# bop_pcb.net
KiCad netlist of a schematic drawn in EAGLE
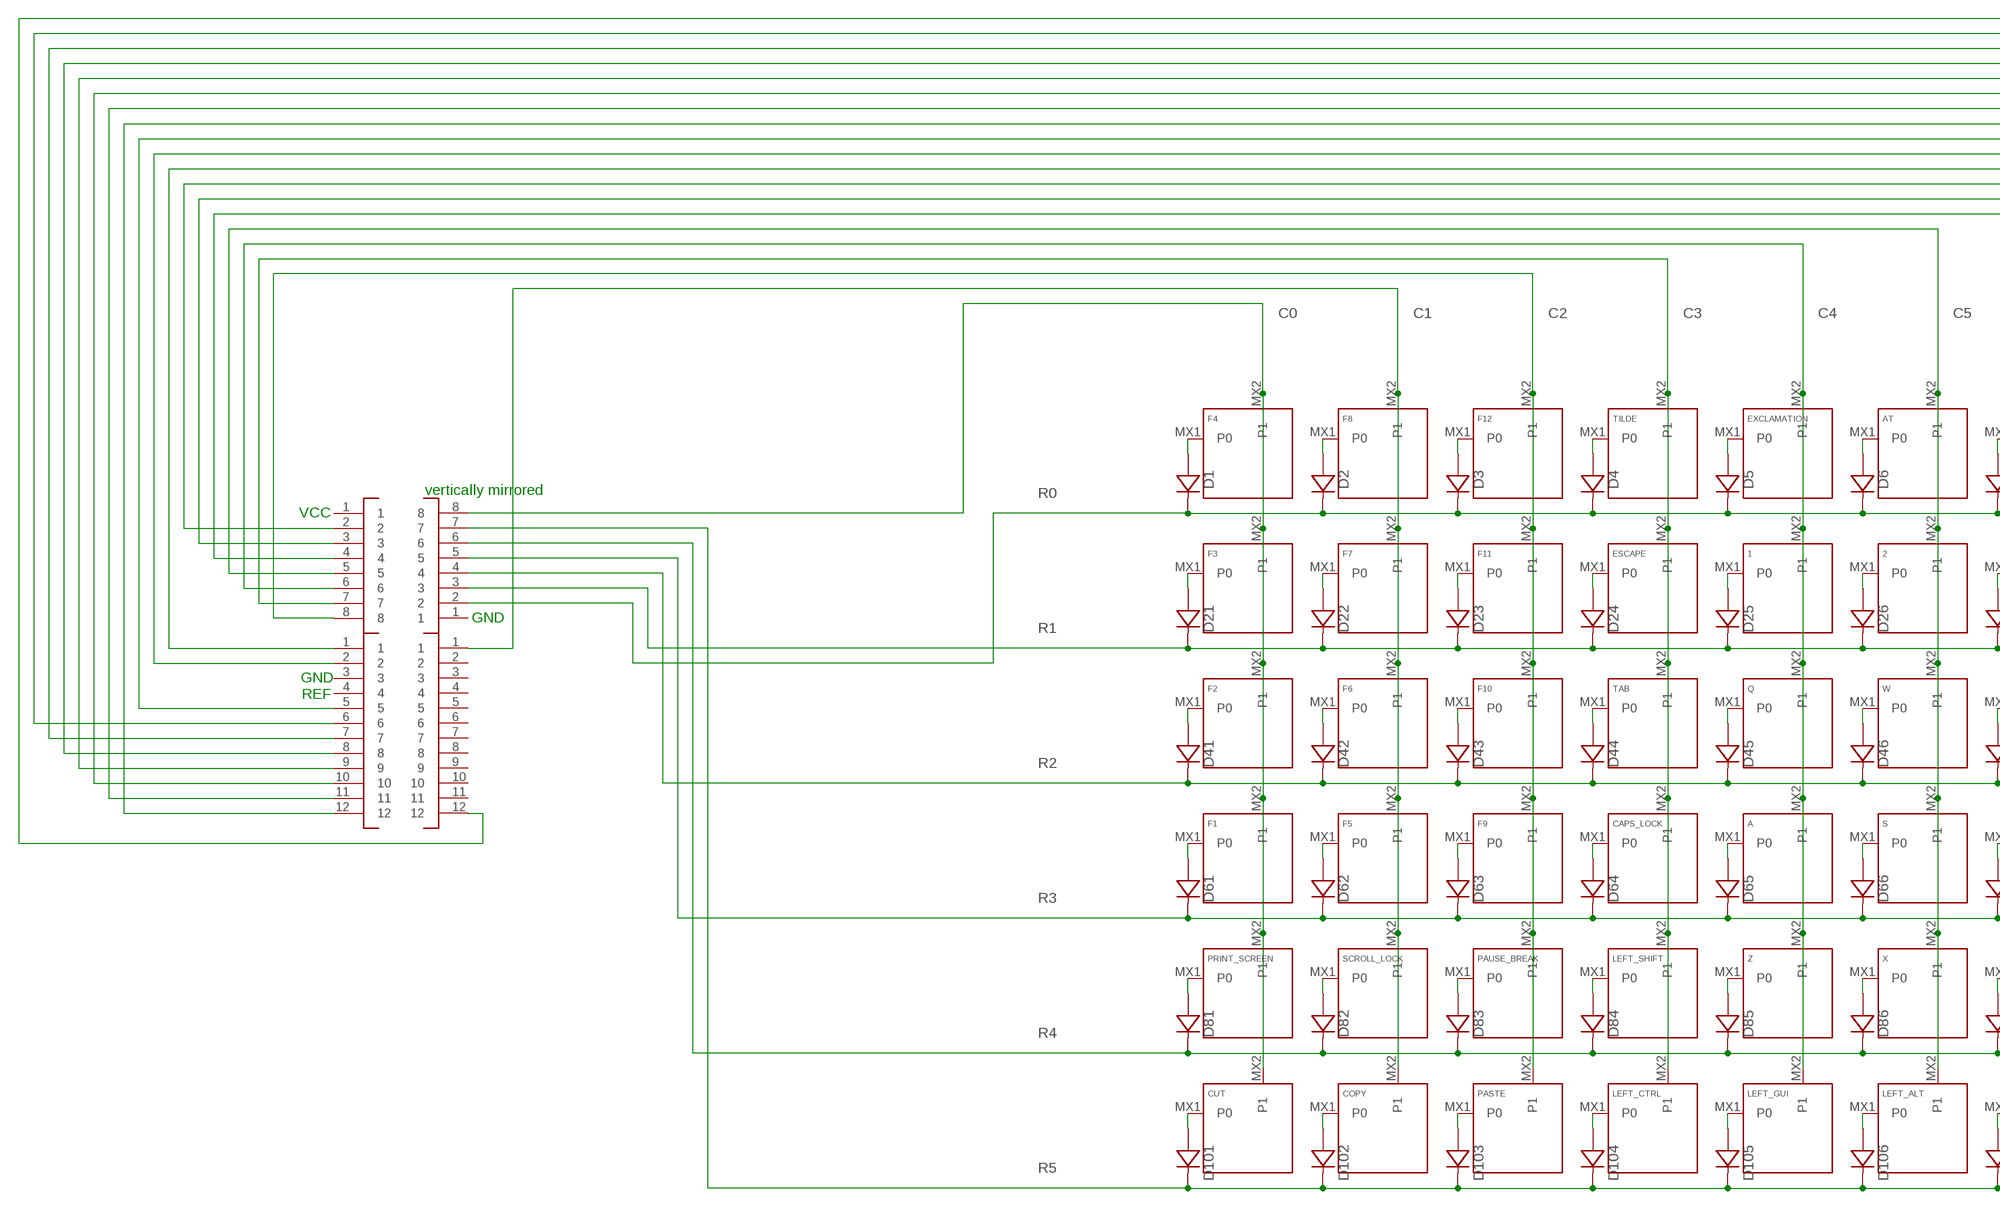
[diagram p0: schematic, sheet 1, part 1 of 2]
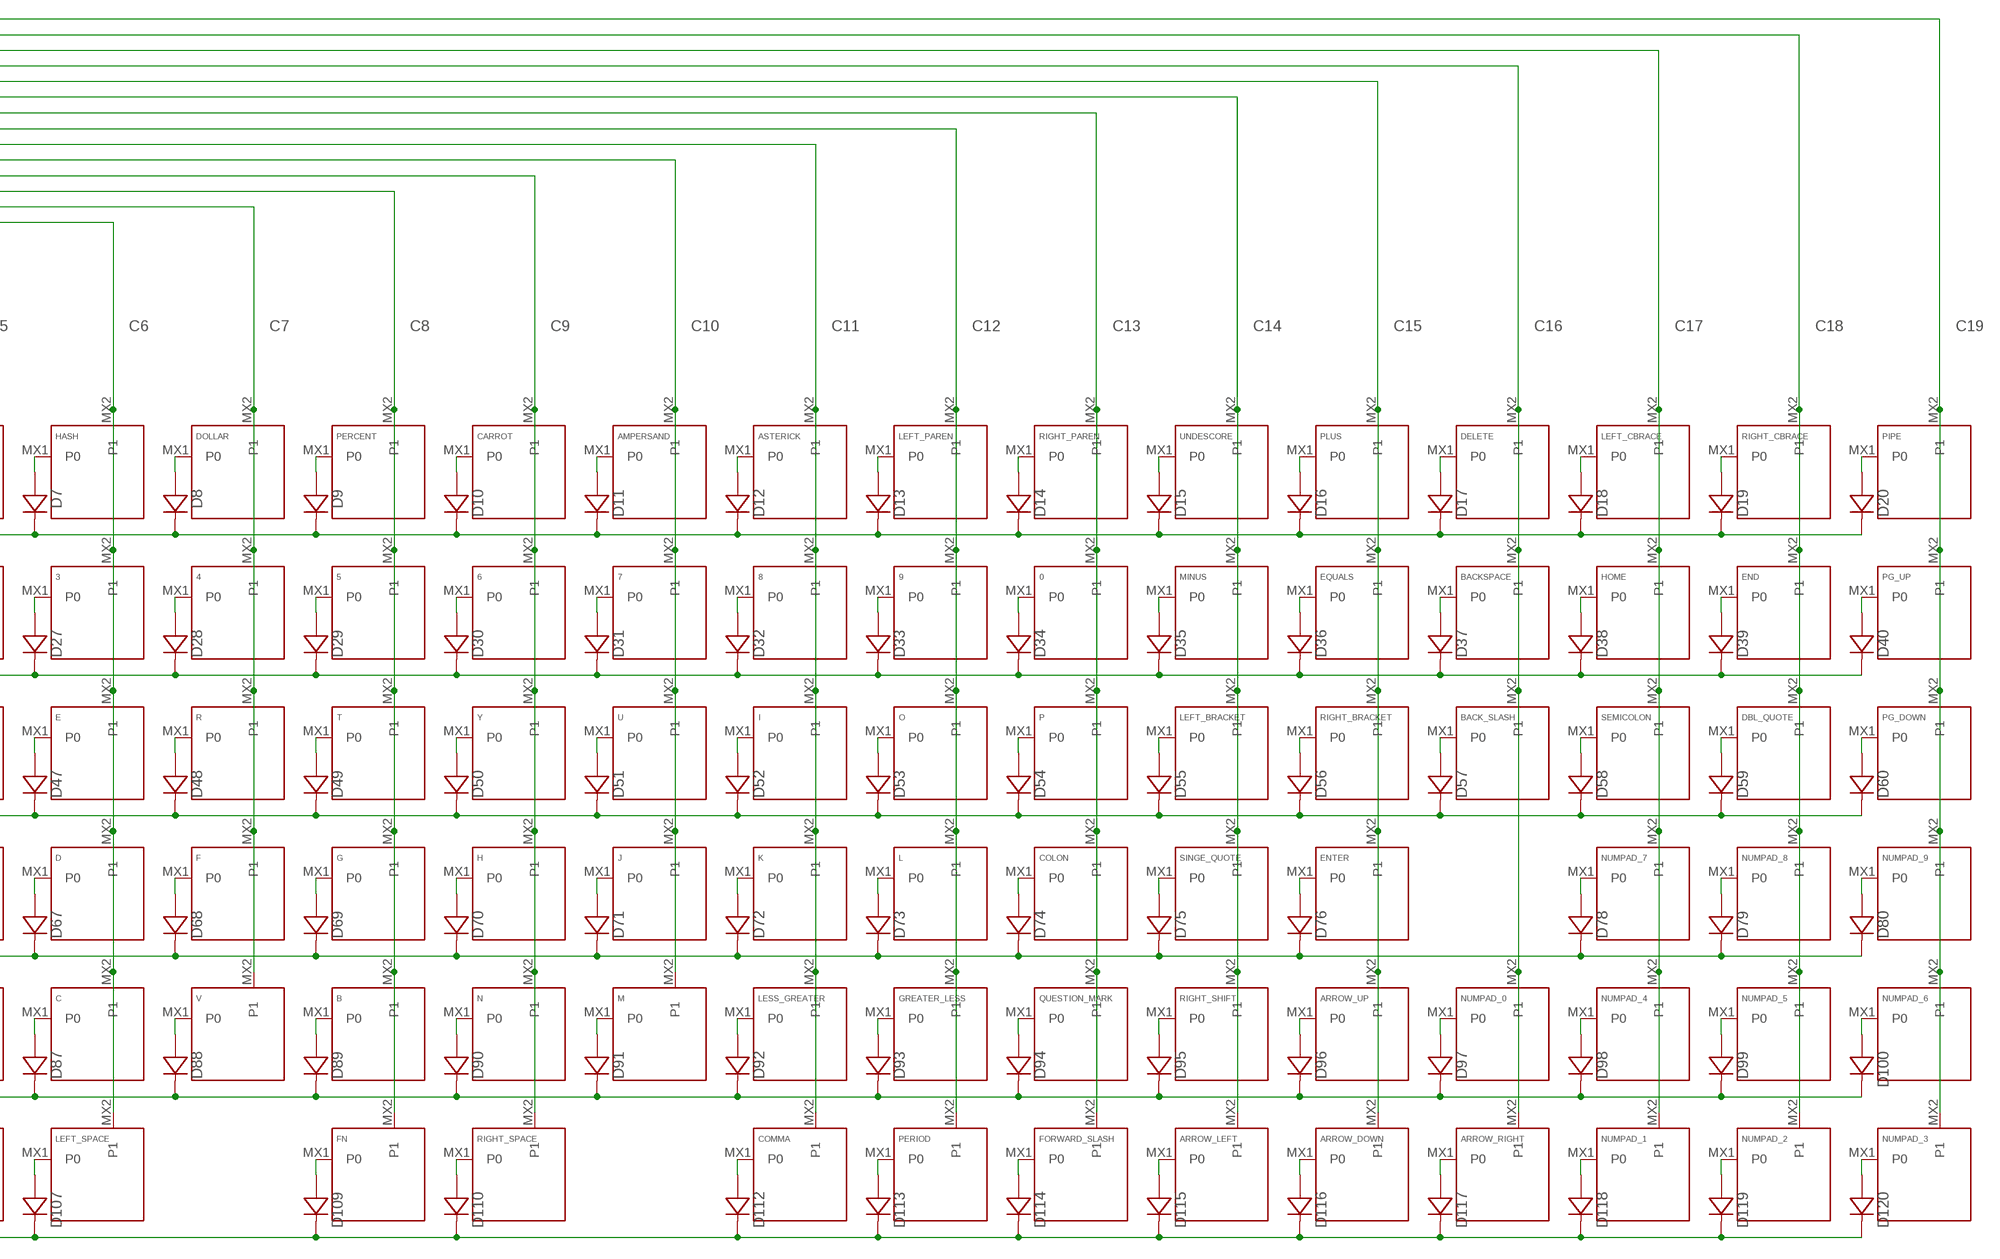
[diagram p1: schematic, sheet 1, part 2 of 2]

(export (version "E")
  (design (tool "Eeschema 10.0.6"))
  (components
    (comp (ref "0")
      (value "KEYSWITCH-PLAIN-MX-1U")
      (footprint "eagle-import:MX-1U")
      (libsource (lib "eagle-import") (part "KEYSWITCH-PLAIN-MX-1U"))
    )
    (comp (ref "1")
      (value "KEYSWITCH-PLAIN-MX-1U")
      (footprint "eagle-import:MX-1U")
      (libsource (lib "eagle-import") (part "KEYSWITCH-PLAIN-MX-1U"))
    )
    (comp (ref "2")
      (value "KEYSWITCH-PLAIN-MX-1U")
      (footprint "eagle-import:MX-1U")
      (libsource (lib "eagle-import") (part "KEYSWITCH-PLAIN-MX-1U"))
    )
    (comp (ref "3")
      (value "KEYSWITCH-PLAIN-MX-1U")
      (footprint "eagle-import:MX-1U")
      (libsource (lib "eagle-import") (part "KEYSWITCH-PLAIN-MX-1U"))
    )
    (comp (ref "4")
      (value "KEYSWITCH-PLAIN-MX-1U")
      (footprint "eagle-import:MX-1U")
      (libsource (lib "eagle-import") (part "KEYSWITCH-PLAIN-MX-1U"))
    )
    (comp (ref "5")
      (value "KEYSWITCH-PLAIN-MX-1U")
      (footprint "eagle-import:MX-1U")
      (libsource (lib "eagle-import") (part "KEYSWITCH-PLAIN-MX-1U"))
    )
    (comp (ref "6")
      (value "KEYSWITCH-PLAIN-MX-1U")
      (footprint "eagle-import:MX-1U")
      (libsource (lib "eagle-import") (part "KEYSWITCH-PLAIN-MX-1U"))
    )
    (comp (ref "7")
      (value "KEYSWITCH-PLAIN-MX-1U")
      (footprint "eagle-import:MX-1U")
      (libsource (lib "eagle-import") (part "KEYSWITCH-PLAIN-MX-1U"))
    )
    (comp (ref "8")
      (value "KEYSWITCH-PLAIN-MX-1U")
      (footprint "eagle-import:MX-1U")
      (libsource (lib "eagle-import") (part "KEYSWITCH-PLAIN-MX-1U"))
    )
    (comp (ref "9")
      (value "KEYSWITCH-PLAIN-MX-1U")
      (footprint "eagle-import:MX-1U")
      (libsource (lib "eagle-import") (part "KEYSWITCH-PLAIN-MX-1U"))
    )
    (comp (ref "A")
      (value "KEYSWITCH-PLAIN-MX-1U")
      (footprint "eagle-import:MX-1U")
      (libsource (lib "eagle-import") (part "KEYSWITCH-PLAIN-MX-1U"))
    )
    (comp (ref "AMPERSAND")
      (value "KEYSWITCH-PLAIN-MX-1U")
      (footprint "eagle-import:MX-1U")
      (libsource (lib "eagle-import") (part "KEYSWITCH-PLAIN-MX-1U"))
    )
    (comp (ref "ARROW_DOWN")
      (value "KEYSWITCH-PLAIN-MX-1U")
      (footprint "eagle-import:MX-1U")
      (libsource (lib "eagle-import") (part "KEYSWITCH-PLAIN-MX-1U"))
    )
    (comp (ref "ARROW_LEFT")
      (value "KEYSWITCH-PLAIN-MX-1U")
      (footprint "eagle-import:MX-1U")
      (libsource (lib "eagle-import") (part "KEYSWITCH-PLAIN-MX-1U"))
    )
    (comp (ref "ARROW_RIGHT")
      (value "KEYSWITCH-PLAIN-MX-1U")
      (footprint "eagle-import:MX-1U")
      (libsource (lib "eagle-import") (part "KEYSWITCH-PLAIN-MX-1U"))
    )
    (comp (ref "ARROW_UP")
      (value "KEYSWITCH-PLAIN-MX-1U")
      (footprint "eagle-import:MX-1U")
      (libsource (lib "eagle-import") (part "KEYSWITCH-PLAIN-MX-1U"))
    )
    (comp (ref "ASTERICK")
      (value "KEYSWITCH-PLAIN-MX-1U")
      (footprint "eagle-import:MX-1U")
      (libsource (lib "eagle-import") (part "KEYSWITCH-PLAIN-MX-1U"))
    )
    (comp (ref "AT")
      (value "KEYSWITCH-PLAIN-MX-1U")
      (footprint "eagle-import:MX-1U")
      (libsource (lib "eagle-import") (part "KEYSWITCH-PLAIN-MX-1U"))
    )
    (comp (ref "B")
      (value "KEYSWITCH-PLAIN-MX-1U")
      (footprint "eagle-import:MX-1U")
      (libsource (lib "eagle-import") (part "KEYSWITCH-PLAIN-MX-1U"))
    )
    (comp (ref "BACKSPACE")
      (value "KEYSWITCH-PLAIN-MX-1U")
      (footprint "eagle-import:MX-1U")
      (libsource (lib "eagle-import") (part "KEYSWITCH-PLAIN-MX-1U"))
    )
    (comp (ref "BACK_SLASH")
      (value "KEYSWITCH-PLAIN-MX-1U")
      (footprint "eagle-import:MX-1U")
      (libsource (lib "eagle-import") (part "KEYSWITCH-PLAIN-MX-1U"))
    )
    (comp (ref "C")
      (value "KEYSWITCH-PLAIN-MX-1U")
      (footprint "eagle-import:MX-1U")
      (libsource (lib "eagle-import") (part "KEYSWITCH-PLAIN-MX-1U"))
    )
    (comp (ref "CAPS_LOCK")
      (value "KEYSWITCH-PLAIN-MX-1U")
      (footprint "eagle-import:MX-1U")
      (libsource (lib "eagle-import") (part "KEYSWITCH-PLAIN-MX-1U"))
    )
    (comp (ref "CARROT")
      (value "KEYSWITCH-PLAIN-MX-1U")
      (footprint "eagle-import:MX-1U")
      (libsource (lib "eagle-import") (part "KEYSWITCH-PLAIN-MX-1U"))
    )
    (comp (ref "COLON")
      (value "KEYSWITCH-PLAIN-MX-1U")
      (footprint "eagle-import:MX-1U")
      (libsource (lib "eagle-import") (part "KEYSWITCH-PLAIN-MX-1U"))
    )
    (comp (ref "COMMA")
      (value "KEYSWITCH-PLAIN-MX-1U")
      (footprint "eagle-import:MX-1U")
      (libsource (lib "eagle-import") (part "KEYSWITCH-PLAIN-MX-1U"))
    )
    (comp (ref "COPY")
      (value "KEYSWITCH-PLAIN-MX-1U")
      (footprint "eagle-import:MX-1U")
      (libsource (lib "eagle-import") (part "KEYSWITCH-PLAIN-MX-1U"))
    )
    (comp (ref "CUT")
      (value "KEYSWITCH-PLAIN-MX-1U")
      (footprint "eagle-import:MX-1U")
      (libsource (lib "eagle-import") (part "KEYSWITCH-PLAIN-MX-1U"))
    )
    (comp (ref "D")
      (value "KEYSWITCH-PLAIN-MX-1U")
      (footprint "eagle-import:MX-1U")
      (libsource (lib "eagle-import") (part "KEYSWITCH-PLAIN-MX-1U"))
    )
    (comp (ref "D1")
      (value "DIODE-SOD-123")
      (footprint "eagle-import:SOD-123")
      (libsource (lib "eagle-import") (part "DIODE-SOD-123"))
    )
    (comp (ref "D2")
      (value "DIODE-SOD-123")
      (footprint "eagle-import:SOD-123")
      (libsource (lib "eagle-import") (part "DIODE-SOD-123"))
    )
    (comp (ref "D3")
      (value "DIODE-SOD-123")
      (footprint "eagle-import:SOD-123")
      (libsource (lib "eagle-import") (part "DIODE-SOD-123"))
    )
    (comp (ref "D4")
      (value "DIODE-SOD-123")
      (footprint "eagle-import:SOD-123")
      (libsource (lib "eagle-import") (part "DIODE-SOD-123"))
    )
    (comp (ref "D5")
      (value "DIODE-SOD-123")
      (footprint "eagle-import:SOD-123")
      (libsource (lib "eagle-import") (part "DIODE-SOD-123"))
    )
    (comp (ref "D6")
      (value "DIODE-SOD-123")
      (footprint "eagle-import:SOD-123")
      (libsource (lib "eagle-import") (part "DIODE-SOD-123"))
    )
    (comp (ref "D7")
      (value "DIODE-SOD-123")
      (footprint "eagle-import:SOD-123")
      (libsource (lib "eagle-import") (part "DIODE-SOD-123"))
    )
    (comp (ref "D8")
      (value "DIODE-SOD-123")
      (footprint "eagle-import:SOD-123")
      (libsource (lib "eagle-import") (part "DIODE-SOD-123"))
    )
    (comp (ref "D9")
      (value "DIODE-SOD-123")
      (footprint "eagle-import:SOD-123")
      (libsource (lib "eagle-import") (part "DIODE-SOD-123"))
    )
    (comp (ref "D10")
      (value "DIODE-SOD-123")
      (footprint "eagle-import:SOD-123")
      (libsource (lib "eagle-import") (part "DIODE-SOD-123"))
    )
    (comp (ref "D11")
      (value "DIODE-SOD-123")
      (footprint "eagle-import:SOD-123")
      (libsource (lib "eagle-import") (part "DIODE-SOD-123"))
    )
    (comp (ref "D12")
      (value "DIODE-SOD-123")
      (footprint "eagle-import:SOD-123")
      (libsource (lib "eagle-import") (part "DIODE-SOD-123"))
    )
    (comp (ref "D13")
      (value "DIODE-SOD-123")
      (footprint "eagle-import:SOD-123")
      (libsource (lib "eagle-import") (part "DIODE-SOD-123"))
    )
    (comp (ref "D14")
      (value "DIODE-SOD-123")
      (footprint "eagle-import:SOD-123")
      (libsource (lib "eagle-import") (part "DIODE-SOD-123"))
    )
    (comp (ref "D15")
      (value "DIODE-SOD-123")
      (footprint "eagle-import:SOD-123")
      (libsource (lib "eagle-import") (part "DIODE-SOD-123"))
    )
    (comp (ref "D16")
      (value "DIODE-SOD-123")
      (footprint "eagle-import:SOD-123")
      (libsource (lib "eagle-import") (part "DIODE-SOD-123"))
    )
    (comp (ref "D17")
      (value "DIODE-SOD-123")
      (footprint "eagle-import:SOD-123")
      (libsource (lib "eagle-import") (part "DIODE-SOD-123"))
    )
    (comp (ref "D18")
      (value "DIODE-SOD-123")
      (footprint "eagle-import:SOD-123")
      (libsource (lib "eagle-import") (part "DIODE-SOD-123"))
    )
    (comp (ref "D19")
      (value "DIODE-SOD-123")
      (footprint "eagle-import:SOD-123")
      (libsource (lib "eagle-import") (part "DIODE-SOD-123"))
    )
    (comp (ref "D20")
      (value "DIODE-SOD-123")
      (footprint "eagle-import:SOD-123")
      (libsource (lib "eagle-import") (part "DIODE-SOD-123"))
    )
    (comp (ref "D21")
      (value "DIODE-SOD-123")
      (footprint "eagle-import:SOD-123")
      (libsource (lib "eagle-import") (part "DIODE-SOD-123"))
    )
    (comp (ref "D22")
      (value "DIODE-SOD-123")
      (footprint "eagle-import:SOD-123")
      (libsource (lib "eagle-import") (part "DIODE-SOD-123"))
    )
    (comp (ref "D23")
      (value "DIODE-SOD-123")
      (footprint "eagle-import:SOD-123")
      (libsource (lib "eagle-import") (part "DIODE-SOD-123"))
    )
    (comp (ref "D24")
      (value "DIODE-SOD-123")
      (footprint "eagle-import:SOD-123")
      (libsource (lib "eagle-import") (part "DIODE-SOD-123"))
    )
    (comp (ref "D25")
      (value "DIODE-SOD-123")
      (footprint "eagle-import:SOD-123")
      (libsource (lib "eagle-import") (part "DIODE-SOD-123"))
    )
    (comp (ref "D26")
      (value "DIODE-SOD-123")
      (footprint "eagle-import:SOD-123")
      (libsource (lib "eagle-import") (part "DIODE-SOD-123"))
    )
    (comp (ref "D27")
      (value "DIODE-SOD-123")
      (footprint "eagle-import:SOD-123")
      (libsource (lib "eagle-import") (part "DIODE-SOD-123"))
    )
    (comp (ref "D28")
      (value "DIODE-SOD-123")
      (footprint "eagle-import:SOD-123")
      (libsource (lib "eagle-import") (part "DIODE-SOD-123"))
    )
    (comp (ref "D29")
      (value "DIODE-SOD-123")
      (footprint "eagle-import:SOD-123")
      (libsource (lib "eagle-import") (part "DIODE-SOD-123"))
    )
    (comp (ref "D30")
      (value "DIODE-SOD-123")
      (footprint "eagle-import:SOD-123")
      (libsource (lib "eagle-import") (part "DIODE-SOD-123"))
    )
    (comp (ref "D31")
      (value "DIODE-SOD-123")
      (footprint "eagle-import:SOD-123")
      (libsource (lib "eagle-import") (part "DIODE-SOD-123"))
    )
    (comp (ref "D32")
      (value "DIODE-SOD-123")
      (footprint "eagle-import:SOD-123")
      (libsource (lib "eagle-import") (part "DIODE-SOD-123"))
    )
    (comp (ref "D33")
      (value "DIODE-SOD-123")
      (footprint "eagle-import:SOD-123")
      (libsource (lib "eagle-import") (part "DIODE-SOD-123"))
    )
    (comp (ref "D34")
      (value "DIODE-SOD-123")
      (footprint "eagle-import:SOD-123")
      (libsource (lib "eagle-import") (part "DIODE-SOD-123"))
    )
    (comp (ref "D35")
      (value "DIODE-SOD-123")
      (footprint "eagle-import:SOD-123")
      (libsource (lib "eagle-import") (part "DIODE-SOD-123"))
    )
    (comp (ref "D36")
      (value "DIODE-SOD-123")
      (footprint "eagle-import:SOD-123")
      (libsource (lib "eagle-import") (part "DIODE-SOD-123"))
    )
    (comp (ref "D37")
      (value "DIODE-SOD-123")
      (footprint "eagle-import:SOD-123")
      (libsource (lib "eagle-import") (part "DIODE-SOD-123"))
    )
    (comp (ref "D38")
      (value "DIODE-SOD-123")
      (footprint "eagle-import:SOD-123")
      (libsource (lib "eagle-import") (part "DIODE-SOD-123"))
    )
    (comp (ref "D39")
      (value "DIODE-SOD-123")
      (footprint "eagle-import:SOD-123")
      (libsource (lib "eagle-import") (part "DIODE-SOD-123"))
    )
    (comp (ref "D40")
      (value "DIODE-SOD-123")
      (footprint "eagle-import:SOD-123")
      (libsource (lib "eagle-import") (part "DIODE-SOD-123"))
    )
    (comp (ref "D41")
      (value "DIODE-SOD-123")
      (footprint "eagle-import:SOD-123")
      (libsource (lib "eagle-import") (part "DIODE-SOD-123"))
    )
    (comp (ref "D42")
      (value "DIODE-SOD-123")
      (footprint "eagle-import:SOD-123")
      (libsource (lib "eagle-import") (part "DIODE-SOD-123"))
    )
    (comp (ref "D43")
      (value "DIODE-SOD-123")
      (footprint "eagle-import:SOD-123")
      (libsource (lib "eagle-import") (part "DIODE-SOD-123"))
    )
    (comp (ref "D44")
      (value "DIODE-SOD-123")
      (footprint "eagle-import:SOD-123")
      (libsource (lib "eagle-import") (part "DIODE-SOD-123"))
    )
    (comp (ref "D45")
      (value "DIODE-SOD-123")
      (footprint "eagle-import:SOD-123")
      (libsource (lib "eagle-import") (part "DIODE-SOD-123"))
    )
    (comp (ref "D46")
      (value "DIODE-SOD-123")
      (footprint "eagle-import:SOD-123")
      (libsource (lib "eagle-import") (part "DIODE-SOD-123"))
    )
    (comp (ref "D47")
      (value "DIODE-SOD-123")
      (footprint "eagle-import:SOD-123")
      (libsource (lib "eagle-import") (part "DIODE-SOD-123"))
    )
    (comp (ref "D48")
      (value "DIODE-SOD-123")
      (footprint "eagle-import:SOD-123")
      (libsource (lib "eagle-import") (part "DIODE-SOD-123"))
    )
    (comp (ref "D49")
      (value "DIODE-SOD-123")
      (footprint "eagle-import:SOD-123")
      (libsource (lib "eagle-import") (part "DIODE-SOD-123"))
    )
    (comp (ref "D50")
      (value "DIODE-SOD-123")
      (footprint "eagle-import:SOD-123")
      (libsource (lib "eagle-import") (part "DIODE-SOD-123"))
    )
    (comp (ref "D51")
      (value "DIODE-SOD-123")
      (footprint "eagle-import:SOD-123")
      (libsource (lib "eagle-import") (part "DIODE-SOD-123"))
    )
    (comp (ref "D52")
      (value "DIODE-SOD-123")
      (footprint "eagle-import:SOD-123")
      (libsource (lib "eagle-import") (part "DIODE-SOD-123"))
    )
    (comp (ref "D53")
      (value "DIODE-SOD-123")
      (footprint "eagle-import:SOD-123")
      (libsource (lib "eagle-import") (part "DIODE-SOD-123"))
    )
    (comp (ref "D54")
      (value "DIODE-SOD-123")
      (footprint "eagle-import:SOD-123")
      (libsource (lib "eagle-import") (part "DIODE-SOD-123"))
    )
    (comp (ref "D55")
      (value "DIODE-SOD-123")
      (footprint "eagle-import:SOD-123")
      (libsource (lib "eagle-import") (part "DIODE-SOD-123"))
    )
    (comp (ref "D56")
      (value "DIODE-SOD-123")
      (footprint "eagle-import:SOD-123")
      (libsource (lib "eagle-import") (part "DIODE-SOD-123"))
    )
    (comp (ref "D57")
      (value "DIODE-SOD-123")
      (footprint "eagle-import:SOD-123")
      (libsource (lib "eagle-import") (part "DIODE-SOD-123"))
    )
    (comp (ref "D58")
      (value "DIODE-SOD-123")
      (footprint "eagle-import:SOD-123")
      (libsource (lib "eagle-import") (part "DIODE-SOD-123"))
    )
    (comp (ref "D59")
      (value "DIODE-SOD-123")
      (footprint "eagle-import:SOD-123")
      (libsource (lib "eagle-import") (part "DIODE-SOD-123"))
    )
    (comp (ref "D60")
      (value "DIODE-SOD-123")
      (footprint "eagle-import:SOD-123")
      (libsource (lib "eagle-import") (part "DIODE-SOD-123"))
    )
    (comp (ref "D61")
      (value "DIODE-SOD-123")
      (footprint "eagle-import:SOD-123")
      (libsource (lib "eagle-import") (part "DIODE-SOD-123"))
    )
    (comp (ref "D62")
      (value "DIODE-SOD-123")
      (footprint "eagle-import:SOD-123")
      (libsource (lib "eagle-import") (part "DIODE-SOD-123"))
    )
    (comp (ref "D63")
      (value "DIODE-SOD-123")
      (footprint "eagle-import:SOD-123")
      (libsource (lib "eagle-import") (part "DIODE-SOD-123"))
    )
    (comp (ref "D64")
      (value "DIODE-SOD-123")
      (footprint "eagle-import:SOD-123")
      (libsource (lib "eagle-import") (part "DIODE-SOD-123"))
    )
    (comp (ref "D65")
      (value "DIODE-SOD-123")
      (footprint "eagle-import:SOD-123")
      (libsource (lib "eagle-import") (part "DIODE-SOD-123"))
    )
    (comp (ref "D66")
      (value "DIODE-SOD-123")
      (footprint "eagle-import:SOD-123")
      (libsource (lib "eagle-import") (part "DIODE-SOD-123"))
    )
    (comp (ref "D67")
      (value "DIODE-SOD-123")
      (footprint "eagle-import:SOD-123")
      (libsource (lib "eagle-import") (part "DIODE-SOD-123"))
    )
    (comp (ref "D68")
      (value "DIODE-SOD-123")
      (footprint "eagle-import:SOD-123")
      (libsource (lib "eagle-import") (part "DIODE-SOD-123"))
    )
    (comp (ref "D69")
      (value "DIODE-SOD-123")
      (footprint "eagle-import:SOD-123")
      (libsource (lib "eagle-import") (part "DIODE-SOD-123"))
    )
    (comp (ref "D70")
      (value "DIODE-SOD-123")
      (footprint "eagle-import:SOD-123")
      (libsource (lib "eagle-import") (part "DIODE-SOD-123"))
    )
    (comp (ref "D71")
      (value "DIODE-SOD-123")
      (footprint "eagle-import:SOD-123")
      (libsource (lib "eagle-import") (part "DIODE-SOD-123"))
    )
    (comp (ref "D72")
      (value "DIODE-SOD-123")
      (footprint "eagle-import:SOD-123")
      (libsource (lib "eagle-import") (part "DIODE-SOD-123"))
    )
    (comp (ref "D73")
      (value "DIODE-SOD-123")
      (footprint "eagle-import:SOD-123")
      (libsource (lib "eagle-import") (part "DIODE-SOD-123"))
    )
    (comp (ref "D74")
      (value "DIODE-SOD-123")
      (footprint "eagle-import:SOD-123")
      (libsource (lib "eagle-import") (part "DIODE-SOD-123"))
    )
    (comp (ref "D75")
      (value "DIODE-SOD-123")
      (footprint "eagle-import:SOD-123")
      (libsource (lib "eagle-import") (part "DIODE-SOD-123"))
    )
    (comp (ref "D76")
      (value "DIODE-SOD-123")
      (footprint "eagle-import:SOD-123")
      (libsource (lib "eagle-import") (part "DIODE-SOD-123"))
    )
    (comp (ref "D78")
      (value "DIODE-SOD-123")
      (footprint "eagle-import:SOD-123")
      (libsource (lib "eagle-import") (part "DIODE-SOD-123"))
    )
    (comp (ref "D79")
      (value "DIODE-SOD-123")
      (footprint "eagle-import:SOD-123")
      (libsource (lib "eagle-import") (part "DIODE-SOD-123"))
    )
    (comp (ref "D80")
      (value "DIODE-SOD-123")
      (footprint "eagle-import:SOD-123")
      (libsource (lib "eagle-import") (part "DIODE-SOD-123"))
    )
    (comp (ref "D81")
      (value "DIODE-SOD-123")
      (footprint "eagle-import:SOD-123")
      (libsource (lib "eagle-import") (part "DIODE-SOD-123"))
    )
    (comp (ref "D82")
      (value "DIODE-SOD-123")
      (footprint "eagle-import:SOD-123")
      (libsource (lib "eagle-import") (part "DIODE-SOD-123"))
    )
    (comp (ref "D83")
      (value "DIODE-SOD-123")
      (footprint "eagle-import:SOD-123")
      (libsource (lib "eagle-import") (part "DIODE-SOD-123"))
    )
    (comp (ref "D84")
      (value "DIODE-SOD-123")
      (footprint "eagle-import:SOD-123")
      (libsource (lib "eagle-import") (part "DIODE-SOD-123"))
    )
    (comp (ref "D85")
      (value "DIODE-SOD-123")
      (footprint "eagle-import:SOD-123")
      (libsource (lib "eagle-import") (part "DIODE-SOD-123"))
    )
    (comp (ref "D86")
      (value "DIODE-SOD-123")
      (footprint "eagle-import:SOD-123")
      (libsource (lib "eagle-import") (part "DIODE-SOD-123"))
    )
    (comp (ref "D87")
      (value "DIODE-SOD-123")
      (footprint "eagle-import:SOD-123")
      (libsource (lib "eagle-import") (part "DIODE-SOD-123"))
    )
    (comp (ref "D88")
      (value "DIODE-SOD-123")
      (footprint "eagle-import:SOD-123")
      (libsource (lib "eagle-import") (part "DIODE-SOD-123"))
    )
    (comp (ref "D89")
      (value "DIODE-SOD-123")
      (footprint "eagle-import:SOD-123")
      (libsource (lib "eagle-import") (part "DIODE-SOD-123"))
    )
    (comp (ref "D90")
      (value "DIODE-SOD-123")
      (footprint "eagle-import:SOD-123")
      (libsource (lib "eagle-import") (part "DIODE-SOD-123"))
    )
    (comp (ref "D91")
      (value "DIODE-SOD-123")
      (footprint "eagle-import:SOD-123")
      (libsource (lib "eagle-import") (part "DIODE-SOD-123"))
    )
    (comp (ref "D92")
      (value "DIODE-SOD-123")
      (footprint "eagle-import:SOD-123")
      (libsource (lib "eagle-import") (part "DIODE-SOD-123"))
    )
    (comp (ref "D93")
      (value "DIODE-SOD-123")
      (footprint "eagle-import:SOD-123")
      (libsource (lib "eagle-import") (part "DIODE-SOD-123"))
    )
    (comp (ref "D94")
      (value "DIODE-SOD-123")
      (footprint "eagle-import:SOD-123")
      (libsource (lib "eagle-import") (part "DIODE-SOD-123"))
    )
    (comp (ref "D95")
      (value "DIODE-SOD-123")
      (footprint "eagle-import:SOD-123")
      (libsource (lib "eagle-import") (part "DIODE-SOD-123"))
    )
    (comp (ref "D96")
      (value "DIODE-SOD-123")
      (footprint "eagle-import:SOD-123")
      (libsource (lib "eagle-import") (part "DIODE-SOD-123"))
    )
    (comp (ref "D97")
      (value "DIODE-SOD-123")
      (footprint "eagle-import:SOD-123")
      (libsource (lib "eagle-import") (part "DIODE-SOD-123"))
    )
    (comp (ref "D98")
      (value "DIODE-SOD-123")
      (footprint "eagle-import:SOD-123")
      (libsource (lib "eagle-import") (part "DIODE-SOD-123"))
    )
    (comp (ref "D99")
      (value "DIODE-SOD-123")
      (footprint "eagle-import:SOD-123")
      (libsource (lib "eagle-import") (part "DIODE-SOD-123"))
    )
    (comp (ref "D100")
      (value "DIODE-SOD-123")
      (footprint "eagle-import:SOD-123")
      (libsource (lib "eagle-import") (part "DIODE-SOD-123"))
    )
    (comp (ref "D101")
      (value "DIODE-SOD-123")
      (footprint "eagle-import:SOD-123")
      (libsource (lib "eagle-import") (part "DIODE-SOD-123"))
    )
    (comp (ref "D102")
      (value "DIODE-SOD-123")
      (footprint "eagle-import:SOD-123")
      (libsource (lib "eagle-import") (part "DIODE-SOD-123"))
    )
    (comp (ref "D103")
      (value "DIODE-SOD-123")
      (footprint "eagle-import:SOD-123")
      (libsource (lib "eagle-import") (part "DIODE-SOD-123"))
    )
    (comp (ref "D104")
      (value "DIODE-SOD-123")
      (footprint "eagle-import:SOD-123")
      (libsource (lib "eagle-import") (part "DIODE-SOD-123"))
    )
    (comp (ref "D105")
      (value "DIODE-SOD-123")
      (footprint "eagle-import:SOD-123")
      (libsource (lib "eagle-import") (part "DIODE-SOD-123"))
    )
    (comp (ref "D106")
      (value "DIODE-SOD-123")
      (footprint "eagle-import:SOD-123")
      (libsource (lib "eagle-import") (part "DIODE-SOD-123"))
    )
    (comp (ref "D107")
      (value "DIODE-SOD-123")
      (footprint "eagle-import:SOD-123")
      (libsource (lib "eagle-import") (part "DIODE-SOD-123"))
    )
    (comp (ref "D109")
      (value "DIODE-SOD-123")
      (footprint "eagle-import:SOD-123")
      (libsource (lib "eagle-import") (part "DIODE-SOD-123"))
    )
    (comp (ref "D110")
      (value "DIODE-SOD-123")
      (footprint "eagle-import:SOD-123")
      (libsource (lib "eagle-import") (part "DIODE-SOD-123"))
    )
    (comp (ref "D112")
      (value "DIODE-SOD-123")
      (footprint "eagle-import:SOD-123")
      (libsource (lib "eagle-import") (part "DIODE-SOD-123"))
    )
    (comp (ref "D113")
      (value "DIODE-SOD-123")
      (footprint "eagle-import:SOD-123")
      (libsource (lib "eagle-import") (part "DIODE-SOD-123"))
    )
    (comp (ref "D114")
      (value "DIODE-SOD-123")
      (footprint "eagle-import:SOD-123")
      (libsource (lib "eagle-import") (part "DIODE-SOD-123"))
    )
    (comp (ref "D115")
      (value "DIODE-SOD-123")
      (footprint "eagle-import:SOD-123")
      (libsource (lib "eagle-import") (part "DIODE-SOD-123"))
    )
    (comp (ref "D116")
      (value "DIODE-SOD-123")
      (footprint "eagle-import:SOD-123")
      (libsource (lib "eagle-import") (part "DIODE-SOD-123"))
    )
    (comp (ref "D117")
      (value "DIODE-SOD-123")
      (footprint "eagle-import:SOD-123")
      (libsource (lib "eagle-import") (part "DIODE-SOD-123"))
    )
    (comp (ref "D118")
      (value "DIODE-SOD-123")
      (footprint "eagle-import:SOD-123")
      (libsource (lib "eagle-import") (part "DIODE-SOD-123"))
    )
    (comp (ref "D119")
      (value "DIODE-SOD-123")
      (footprint "eagle-import:SOD-123")
      (libsource (lib "eagle-import") (part "DIODE-SOD-123"))
    )
    (comp (ref "D120")
      (value "DIODE-SOD-123")
      (footprint "eagle-import:SOD-123")
      (libsource (lib "eagle-import") (part "DIODE-SOD-123"))
    )
    (comp (ref "DBL_QUOTE")
      (value "KEYSWITCH-PLAIN-MX-1U")
      (footprint "eagle-import:MX-1U")
      (libsource (lib "eagle-import") (part "KEYSWITCH-PLAIN-MX-1U"))
    )
    (comp (ref "DELETE")
      (value "KEYSWITCH-PLAIN-MX-1U")
      (footprint "eagle-import:MX-1U")
      (libsource (lib "eagle-import") (part "KEYSWITCH-PLAIN-MX-1U"))
    )
    (comp (ref "DOLLAR")
      (value "KEYSWITCH-PLAIN-MX-1U")
      (footprint "eagle-import:MX-1U")
      (libsource (lib "eagle-import") (part "KEYSWITCH-PLAIN-MX-1U"))
    )
    (comp (ref "E")
      (value "KEYSWITCH-PLAIN-MX-1U")
      (footprint "eagle-import:MX-1U")
      (libsource (lib "eagle-import") (part "KEYSWITCH-PLAIN-MX-1U"))
    )
    (comp (ref "END")
      (value "KEYSWITCH-PLAIN-MX-1U")
      (footprint "eagle-import:MX-1U")
      (libsource (lib "eagle-import") (part "KEYSWITCH-PLAIN-MX-1U"))
    )
    (comp (ref "ENTER")
      (value "KEYSWITCH-PLAIN-MX-1U")
      (footprint "eagle-import:MX-1U")
      (libsource (lib "eagle-import") (part "KEYSWITCH-PLAIN-MX-1U"))
    )
    (comp (ref "EQUALS")
      (value "KEYSWITCH-PLAIN-MX-1U")
      (footprint "eagle-import:MX-1U")
      (libsource (lib "eagle-import") (part "KEYSWITCH-PLAIN-MX-1U"))
    )
    (comp (ref "ESCAPE")
      (value "KEYSWITCH-PLAIN-MX-1U")
      (footprint "eagle-import:MX-1U")
      (libsource (lib "eagle-import") (part "KEYSWITCH-PLAIN-MX-1U"))
    )
    (comp (ref "EXCLAMATION")
      (value "KEYSWITCH-PLAIN-MX-1U")
      (footprint "eagle-import:MX-1U")
      (libsource (lib "eagle-import") (part "KEYSWITCH-PLAIN-MX-1U"))
    )
    (comp (ref "F")
      (value "KEYSWITCH-PLAIN-MX-1U")
      (footprint "eagle-import:MX-1U")
      (libsource (lib "eagle-import") (part "KEYSWITCH-PLAIN-MX-1U"))
    )
    (comp (ref "F1")
      (value "KEYSWITCH-PLAIN-MX-1U")
      (footprint "eagle-import:MX-1U")
      (libsource (lib "eagle-import") (part "KEYSWITCH-PLAIN-MX-1U"))
    )
    (comp (ref "F2")
      (value "KEYSWITCH-PLAIN-MX-1U")
      (footprint "eagle-import:MX-1U")
      (libsource (lib "eagle-import") (part "KEYSWITCH-PLAIN-MX-1U"))
    )
    (comp (ref "F3")
      (value "KEYSWITCH-PLAIN-MX-1U")
      (footprint "eagle-import:MX-1U")
      (libsource (lib "eagle-import") (part "KEYSWITCH-PLAIN-MX-1U"))
    )
    (comp (ref "F4")
      (value "KEYSWITCH-PLAIN-MX-1U")
      (footprint "eagle-import:MX-1U")
      (libsource (lib "eagle-import") (part "KEYSWITCH-PLAIN-MX-1U"))
    )
    (comp (ref "F5")
      (value "KEYSWITCH-PLAIN-MX-1U")
      (footprint "eagle-import:MX-1U")
      (libsource (lib "eagle-import") (part "KEYSWITCH-PLAIN-MX-1U"))
    )
    (comp (ref "F6")
      (value "KEYSWITCH-PLAIN-MX-1U")
      (footprint "eagle-import:MX-1U")
      (libsource (lib "eagle-import") (part "KEYSWITCH-PLAIN-MX-1U"))
    )
    (comp (ref "F7")
      (value "KEYSWITCH-PLAIN-MX-1U")
      (footprint "eagle-import:MX-1U")
      (libsource (lib "eagle-import") (part "KEYSWITCH-PLAIN-MX-1U"))
    )
    (comp (ref "F8")
      (value "KEYSWITCH-PLAIN-MX-1U")
      (footprint "eagle-import:MX-1U")
      (libsource (lib "eagle-import") (part "KEYSWITCH-PLAIN-MX-1U"))
    )
    (comp (ref "F9")
      (value "KEYSWITCH-PLAIN-MX-1U")
      (footprint "eagle-import:MX-1U")
      (libsource (lib "eagle-import") (part "KEYSWITCH-PLAIN-MX-1U"))
    )
    (comp (ref "F10")
      (value "KEYSWITCH-PLAIN-MX-1U")
      (footprint "eagle-import:MX-1U")
      (libsource (lib "eagle-import") (part "KEYSWITCH-PLAIN-MX-1U"))
    )
    (comp (ref "F11")
      (value "KEYSWITCH-PLAIN-MX-1U")
      (footprint "eagle-import:MX-1U")
      (libsource (lib "eagle-import") (part "KEYSWITCH-PLAIN-MX-1U"))
    )
    (comp (ref "F12")
      (value "KEYSWITCH-PLAIN-MX-1U")
      (footprint "eagle-import:MX-1U")
      (libsource (lib "eagle-import") (part "KEYSWITCH-PLAIN-MX-1U"))
    )
    (comp (ref "FN")
      (value "KEYSWITCH-PLAIN-MX-1U")
      (footprint "eagle-import:MX-1U")
      (libsource (lib "eagle-import") (part "KEYSWITCH-PLAIN-MX-1U"))
    )
    (comp (ref "FORWARD_SLASH")
      (value "KEYSWITCH-PLAIN-MX-1U")
      (footprint "eagle-import:MX-1U")
      (libsource (lib "eagle-import") (part "KEYSWITCH-PLAIN-MX-1U"))
    )
    (comp (ref "G")
      (value "KEYSWITCH-PLAIN-MX-1U")
      (footprint "eagle-import:MX-1U")
      (libsource (lib "eagle-import") (part "KEYSWITCH-PLAIN-MX-1U"))
    )
    (comp (ref "GREATER_LESS")
      (value "KEYSWITCH-PLAIN-MX-1U")
      (footprint "eagle-import:MX-1U")
      (libsource (lib "eagle-import") (part "KEYSWITCH-PLAIN-MX-1U"))
    )
    (comp (ref "H")
      (value "KEYSWITCH-PLAIN-MX-1U")
      (footprint "eagle-import:MX-1U")
      (libsource (lib "eagle-import") (part "KEYSWITCH-PLAIN-MX-1U"))
    )
    (comp (ref "HASH")
      (value "KEYSWITCH-PLAIN-MX-1U")
      (footprint "eagle-import:MX-1U")
      (libsource (lib "eagle-import") (part "KEYSWITCH-PLAIN-MX-1U"))
    )
    (comp (ref "HOME")
      (value "KEYSWITCH-PLAIN-MX-1U")
      (footprint "eagle-import:MX-1U")
      (libsource (lib "eagle-import") (part "KEYSWITCH-PLAIN-MX-1U"))
    )
    (comp (ref "I")
      (value "KEYSWITCH-PLAIN-MX-1U")
      (footprint "eagle-import:MX-1U")
      (libsource (lib "eagle-import") (part "KEYSWITCH-PLAIN-MX-1U"))
    )
    (comp (ref "J")
      (value "KEYSWITCH-PLAIN-MX-1U")
      (footprint "eagle-import:MX-1U")
      (libsource (lib "eagle-import") (part "KEYSWITCH-PLAIN-MX-1U"))
    )
    (comp (ref "J1")
      (value "HEADER-12X1-2.54-ROUND")
      (footprint "eagle-import:HEADER-12X1-2.54-ROUND")
      (libsource (lib "eagle-import") (part "HEADER-12X1-2.54-ROUND"))
    )
    (comp (ref "J2")
      (value "HEADER-12X1-2.54-ROUND")
      (footprint "eagle-import:HEADER-12X1-2.54-ROUND")
      (libsource (lib "eagle-import") (part "HEADER-12X1-2.54-ROUND"))
    )
    (comp (ref "K")
      (value "KEYSWITCH-PLAIN-MX-1U")
      (footprint "eagle-import:MX-1U")
      (libsource (lib "eagle-import") (part "KEYSWITCH-PLAIN-MX-1U"))
    )
    (comp (ref "L")
      (value "KEYSWITCH-PLAIN-MX-1U")
      (footprint "eagle-import:MX-1U")
      (libsource (lib "eagle-import") (part "KEYSWITCH-PLAIN-MX-1U"))
    )
    (comp (ref "LEFT_ALT")
      (value "KEYSWITCH-PLAIN-MX-1U")
      (footprint "eagle-import:MX-1U")
      (libsource (lib "eagle-import") (part "KEYSWITCH-PLAIN-MX-1U"))
    )
    (comp (ref "LEFT_BRACKET")
      (value "KEYSWITCH-PLAIN-MX-1U")
      (footprint "eagle-import:MX-1U")
      (libsource (lib "eagle-import") (part "KEYSWITCH-PLAIN-MX-1U"))
    )
    (comp (ref "LEFT_CBRACE")
      (value "KEYSWITCH-PLAIN-MX-1U")
      (footprint "eagle-import:MX-1U")
      (libsource (lib "eagle-import") (part "KEYSWITCH-PLAIN-MX-1U"))
    )
    (comp (ref "LEFT_CTRL")
      (value "KEYSWITCH-PLAIN-MX-1U")
      (footprint "eagle-import:MX-1U")
      (libsource (lib "eagle-import") (part "KEYSWITCH-PLAIN-MX-1U"))
    )
    (comp (ref "LEFT_GUI")
      (value "KEYSWITCH-PLAIN-MX-1U")
      (footprint "eagle-import:MX-1U")
      (libsource (lib "eagle-import") (part "KEYSWITCH-PLAIN-MX-1U"))
    )
    (comp (ref "LEFT_PAREN")
      (value "KEYSWITCH-PLAIN-MX-1U")
      (footprint "eagle-import:MX-1U")
      (libsource (lib "eagle-import") (part "KEYSWITCH-PLAIN-MX-1U"))
    )
    (comp (ref "LEFT_SHIFT")
      (value "KEYSWITCH-PLAIN-MX-1U")
      (footprint "eagle-import:MX-1U")
      (libsource (lib "eagle-import") (part "KEYSWITCH-PLAIN-MX-1U"))
    )
    (comp (ref "LEFT_SPACE")
      (value "KEYSWITCH-PLAIN-MX-2U-FLIPPED")
      (footprint "eagle-import:MX-2U-FLIPPED")
      (libsource (lib "eagle-import") (part "KEYSWITCH-PLAIN-MX-2U-FLIPPED"))
    )
    (comp (ref "LESS_GREATER")
      (value "KEYSWITCH-PLAIN-MX-1U")
      (footprint "eagle-import:MX-1U")
      (libsource (lib "eagle-import") (part "KEYSWITCH-PLAIN-MX-1U"))
    )
    (comp (ref "M")
      (value "KEYSWITCH-PLAIN-MX-1U")
      (footprint "eagle-import:MX-1U")
      (libsource (lib "eagle-import") (part "KEYSWITCH-PLAIN-MX-1U"))
    )
    (comp (ref "MINUS")
      (value "KEYSWITCH-PLAIN-MX-1U")
      (footprint "eagle-import:MX-1U")
      (libsource (lib "eagle-import") (part "KEYSWITCH-PLAIN-MX-1U"))
    )
    (comp (ref "N")
      (value "KEYSWITCH-PLAIN-MX-1U")
      (footprint "eagle-import:MX-1U")
      (libsource (lib "eagle-import") (part "KEYSWITCH-PLAIN-MX-1U"))
    )
    (comp (ref "NUMPAD_0")
      (value "KEYSWITCH-PLAIN-MX-2U-ROTATED")
      (footprint "eagle-import:MX-2U-ROTATED")
      (libsource (lib "eagle-import") (part "KEYSWITCH-PLAIN-MX-2U-ROTATED"))
    )
    (comp (ref "NUMPAD_1")
      (value "KEYSWITCH-PLAIN-MX-1U")
      (footprint "eagle-import:MX-1U")
      (libsource (lib "eagle-import") (part "KEYSWITCH-PLAIN-MX-1U"))
    )
    (comp (ref "NUMPAD_2")
      (value "KEYSWITCH-PLAIN-MX-1U")
      (footprint "eagle-import:MX-1U")
      (libsource (lib "eagle-import") (part "KEYSWITCH-PLAIN-MX-1U"))
    )
    (comp (ref "NUMPAD_3")
      (value "KEYSWITCH-PLAIN-MX-1U")
      (footprint "eagle-import:MX-1U")
      (libsource (lib "eagle-import") (part "KEYSWITCH-PLAIN-MX-1U"))
    )
    (comp (ref "NUMPAD_4")
      (value "KEYSWITCH-PLAIN-MX-1U")
      (footprint "eagle-import:MX-1U")
      (libsource (lib "eagle-import") (part "KEYSWITCH-PLAIN-MX-1U"))
    )
    (comp (ref "NUMPAD_5")
      (value "KEYSWITCH-PLAIN-MX-1U")
      (footprint "eagle-import:MX-1U")
      (libsource (lib "eagle-import") (part "KEYSWITCH-PLAIN-MX-1U"))
    )
    (comp (ref "NUMPAD_6")
      (value "KEYSWITCH-PLAIN-MX-1U")
      (footprint "eagle-import:MX-1U")
      (libsource (lib "eagle-import") (part "KEYSWITCH-PLAIN-MX-1U"))
    )
    (comp (ref "NUMPAD_7")
      (value "KEYSWITCH-PLAIN-MX-1U")
      (footprint "eagle-import:MX-1U")
      (libsource (lib "eagle-import") (part "KEYSWITCH-PLAIN-MX-1U"))
    )
    (comp (ref "NUMPAD_8")
      (value "KEYSWITCH-PLAIN-MX-1U")
      (footprint "eagle-import:MX-1U")
      (libsource (lib "eagle-import") (part "KEYSWITCH-PLAIN-MX-1U"))
    )
    (comp (ref "NUMPAD_9")
      (value "KEYSWITCH-PLAIN-MX-1U")
      (footprint "eagle-import:MX-1U")
      (libsource (lib "eagle-import") (part "KEYSWITCH-PLAIN-MX-1U"))
    )
    (comp (ref "O")
      (value "KEYSWITCH-PLAIN-MX-1U")
      (footprint "eagle-import:MX-1U")
      (libsource (lib "eagle-import") (part "KEYSWITCH-PLAIN-MX-1U"))
    )
    (comp (ref "P")
      (value "KEYSWITCH-PLAIN-MX-1U")
      (footprint "eagle-import:MX-1U")
      (libsource (lib "eagle-import") (part "KEYSWITCH-PLAIN-MX-1U"))
    )
    (comp (ref "PASTE")
      (value "KEYSWITCH-PLAIN-MX-1U")
      (footprint "eagle-import:MX-1U")
      (libsource (lib "eagle-import") (part "KEYSWITCH-PLAIN-MX-1U"))
    )
    (comp (ref "PAUSE_BREAK")
      (value "KEYSWITCH-PLAIN-MX-1U")
      (footprint "eagle-import:MX-1U")
      (libsource (lib "eagle-import") (part "KEYSWITCH-PLAIN-MX-1U"))
    )
    (comp (ref "PERCENT")
      (value "KEYSWITCH-PLAIN-MX-1U")
      (footprint "eagle-import:MX-1U")
      (libsource (lib "eagle-import") (part "KEYSWITCH-PLAIN-MX-1U"))
    )
    (comp (ref "PERIOD")
      (value "KEYSWITCH-PLAIN-MX-1U")
      (footprint "eagle-import:MX-1U")
      (libsource (lib "eagle-import") (part "KEYSWITCH-PLAIN-MX-1U"))
    )
    (comp (ref "PG_DOWN")
      (value "KEYSWITCH-PLAIN-MX-1U")
      (footprint "eagle-import:MX-1U")
      (libsource (lib "eagle-import") (part "KEYSWITCH-PLAIN-MX-1U"))
    )
    (comp (ref "PG_UP")
      (value "KEYSWITCH-PLAIN-MX-1U")
      (footprint "eagle-import:MX-1U")
      (libsource (lib "eagle-import") (part "KEYSWITCH-PLAIN-MX-1U"))
    )
    (comp (ref "PIPE")
      (value "KEYSWITCH-PLAIN-MX-1U")
      (footprint "eagle-import:MX-1U")
      (libsource (lib "eagle-import") (part "KEYSWITCH-PLAIN-MX-1U"))
    )
    (comp (ref "PLUS")
      (value "KEYSWITCH-PLAIN-MX-1U")
      (footprint "eagle-import:MX-1U")
      (libsource (lib "eagle-import") (part "KEYSWITCH-PLAIN-MX-1U"))
    )
    (comp (ref "PRINT_SCREEN")
      (value "KEYSWITCH-PLAIN-MX-1U")
      (footprint "eagle-import:MX-1U")
      (libsource (lib "eagle-import") (part "KEYSWITCH-PLAIN-MX-1U"))
    )
    (comp (ref "Q")
      (value "KEYSWITCH-PLAIN-MX-1U")
      (footprint "eagle-import:MX-1U")
      (libsource (lib "eagle-import") (part "KEYSWITCH-PLAIN-MX-1U"))
    )
    (comp (ref "QUESTION_MARK")
      (value "KEYSWITCH-PLAIN-MX-1U")
      (footprint "eagle-import:MX-1U")
      (libsource (lib "eagle-import") (part "KEYSWITCH-PLAIN-MX-1U"))
    )
    (comp (ref "R")
      (value "KEYSWITCH-PLAIN-MX-1U")
      (footprint "eagle-import:MX-1U")
      (libsource (lib "eagle-import") (part "KEYSWITCH-PLAIN-MX-1U"))
    )
    (comp (ref "RIGHT_BRACKET")
      (value "KEYSWITCH-PLAIN-MX-1U")
      (footprint "eagle-import:MX-1U")
      (libsource (lib "eagle-import") (part "KEYSWITCH-PLAIN-MX-1U"))
    )
    (comp (ref "RIGHT_CBRACE")
      (value "KEYSWITCH-PLAIN-MX-1U")
      (footprint "eagle-import:MX-1U")
      (libsource (lib "eagle-import") (part "KEYSWITCH-PLAIN-MX-1U"))
    )
    (comp (ref "RIGHT_PAREN")
      (value "KEYSWITCH-PLAIN-MX-1U")
      (footprint "eagle-import:MX-1U")
      (libsource (lib "eagle-import") (part "KEYSWITCH-PLAIN-MX-1U"))
    )
    (comp (ref "RIGHT_SHIFT")
      (value "KEYSWITCH-PLAIN-MX-1U")
      (footprint "eagle-import:MX-1U")
      (libsource (lib "eagle-import") (part "KEYSWITCH-PLAIN-MX-1U"))
    )
    (comp (ref "RIGHT_SPACE")
      (value "KEYSWITCH-PLAIN-MX-2U-FLIPPED")
      (footprint "eagle-import:MX-2U-FLIPPED")
      (libsource (lib "eagle-import") (part "KEYSWITCH-PLAIN-MX-2U-FLIPPED"))
    )
    (comp (ref "S")
      (value "KEYSWITCH-PLAIN-MX-1U")
      (footprint "eagle-import:MX-1U")
      (libsource (lib "eagle-import") (part "KEYSWITCH-PLAIN-MX-1U"))
    )
    (comp (ref "SCROLL_LOCK")
      (value "KEYSWITCH-PLAIN-MX-1U")
      (footprint "eagle-import:MX-1U")
      (libsource (lib "eagle-import") (part "KEYSWITCH-PLAIN-MX-1U"))
    )
    (comp (ref "SEMICOLON")
      (value "KEYSWITCH-PLAIN-MX-1U")
      (footprint "eagle-import:MX-1U")
      (libsource (lib "eagle-import") (part "KEYSWITCH-PLAIN-MX-1U"))
    )
    (comp (ref "SINGE_QUOTE")
      (value "KEYSWITCH-PLAIN-MX-1U")
      (footprint "eagle-import:MX-1U")
      (libsource (lib "eagle-import") (part "KEYSWITCH-PLAIN-MX-1U"))
    )
    (comp (ref "T")
      (value "KEYSWITCH-PLAIN-MX-1U")
      (footprint "eagle-import:MX-1U")
      (libsource (lib "eagle-import") (part "KEYSWITCH-PLAIN-MX-1U"))
    )
    (comp (ref "TAB")
      (value "KEYSWITCH-PLAIN-MX-1U")
      (footprint "eagle-import:MX-1U")
      (libsource (lib "eagle-import") (part "KEYSWITCH-PLAIN-MX-1U"))
    )
    (comp (ref "TILDE")
      (value "KEYSWITCH-PLAIN-MX-1U")
      (footprint "eagle-import:MX-1U")
      (libsource (lib "eagle-import") (part "KEYSWITCH-PLAIN-MX-1U"))
    )
    (comp (ref "U")
      (value "KEYSWITCH-PLAIN-MX-1U")
      (footprint "eagle-import:MX-1U")
      (libsource (lib "eagle-import") (part "KEYSWITCH-PLAIN-MX-1U"))
    )
    (comp (ref "U$1")
      (value "HEADER-8X1-2.54")
      (footprint "eagle-import:HEADER-8X1-2.54")
      (libsource (lib "eagle-import") (part "HEADER-8X1-2.54"))
    )
    (comp (ref "U$2")
      (value "HEADER-8X1-2.54")
      (footprint "eagle-import:HEADER-8X1-2.54")
      (libsource (lib "eagle-import") (part "HEADER-8X1-2.54"))
    )
    (comp (ref "UNDESCORE")
      (value "KEYSWITCH-PLAIN-MX-1U")
      (footprint "eagle-import:MX-1U")
      (libsource (lib "eagle-import") (part "KEYSWITCH-PLAIN-MX-1U"))
    )
    (comp (ref "V")
      (value "KEYSWITCH-PLAIN-MX-1U")
      (footprint "eagle-import:MX-1U")
      (libsource (lib "eagle-import") (part "KEYSWITCH-PLAIN-MX-1U"))
    )
    (comp (ref "W")
      (value "KEYSWITCH-PLAIN-MX-1U")
      (footprint "eagle-import:MX-1U")
      (libsource (lib "eagle-import") (part "KEYSWITCH-PLAIN-MX-1U"))
    )
    (comp (ref "X")
      (value "KEYSWITCH-PLAIN-MX-1U")
      (footprint "eagle-import:MX-1U")
      (libsource (lib "eagle-import") (part "KEYSWITCH-PLAIN-MX-1U"))
    )
    (comp (ref "Y")
      (value "KEYSWITCH-PLAIN-MX-1U")
      (footprint "eagle-import:MX-1U")
      (libsource (lib "eagle-import") (part "KEYSWITCH-PLAIN-MX-1U"))
    )
    (comp (ref "Z")
      (value "KEYSWITCH-PLAIN-MX-1U")
      (footprint "eagle-import:MX-1U")
      (libsource (lib "eagle-import") (part "KEYSWITCH-PLAIN-MX-1U"))
    )
  )
  (nets
    (net (code "1") (name "/C0") (class "Default")
      (node (ref "CUT") (pin "MX2") (pinfunction "P1_MX2") (pintype "bidirectional"))
      (node (ref "F1") (pin "MX2") (pinfunction "P1_MX2") (pintype "bidirectional"))
      (node (ref "F2") (pin "MX2") (pinfunction "P1_MX2") (pintype "bidirectional"))
      (node (ref "F3") (pin "MX2") (pinfunction "P1_MX2") (pintype "bidirectional"))
      (node (ref "F4") (pin "MX2") (pinfunction "P1_MX2") (pintype "bidirectional"))
      (node (ref "PRINT_SCREEN") (pin "MX2") (pinfunction "P1_MX2") (pintype "bidirectional"))
      (node (ref "U$2") (pin "8") (pinfunction "8_8") (pintype "bidirectional"))
    )
    (net (code "2") (name "/C1") (class "Default")
      (node (ref "COPY") (pin "MX2") (pinfunction "P1_MX2") (pintype "bidirectional"))
      (node (ref "F5") (pin "MX2") (pinfunction "P1_MX2") (pintype "bidirectional"))
      (node (ref "F6") (pin "MX2") (pinfunction "P1_MX2") (pintype "bidirectional"))
      (node (ref "F7") (pin "MX2") (pinfunction "P1_MX2") (pintype "bidirectional"))
      (node (ref "F8") (pin "MX2") (pinfunction "P1_MX2") (pintype "bidirectional"))
      (node (ref "J1") (pin "1") (pinfunction "1_1") (pintype "bidirectional"))
      (node (ref "SCROLL_LOCK") (pin "MX2") (pinfunction "P1_MX2") (pintype "bidirectional"))
    )
    (net (code "3") (name "/C2") (class "Default")
      (node (ref "F10") (pin "MX2") (pinfunction "P1_MX2") (pintype "bidirectional"))
      (node (ref "F11") (pin "MX2") (pinfunction "P1_MX2") (pintype "bidirectional"))
      (node (ref "F12") (pin "MX2") (pinfunction "P1_MX2") (pintype "bidirectional"))
      (node (ref "F9") (pin "MX2") (pinfunction "P1_MX2") (pintype "bidirectional"))
      (node (ref "PASTE") (pin "MX2") (pinfunction "P1_MX2") (pintype "bidirectional"))
      (node (ref "PAUSE_BREAK") (pin "MX2") (pinfunction "P1_MX2") (pintype "bidirectional"))
      (node (ref "U$1") (pin "8") (pinfunction "8_8") (pintype "bidirectional"))
    )
    (net (code "4") (name "/C3") (class "Default")
      (node (ref "CAPS_LOCK") (pin "MX2") (pinfunction "P1_MX2") (pintype "bidirectional"))
      (node (ref "ESCAPE") (pin "MX2") (pinfunction "P1_MX2") (pintype "bidirectional"))
      (node (ref "LEFT_CTRL") (pin "MX2") (pinfunction "P1_MX2") (pintype "bidirectional"))
      (node (ref "LEFT_SHIFT") (pin "MX2") (pinfunction "P1_MX2") (pintype "bidirectional"))
      (node (ref "TAB") (pin "MX2") (pinfunction "P1_MX2") (pintype "bidirectional"))
      (node (ref "TILDE") (pin "MX2") (pinfunction "P1_MX2") (pintype "bidirectional"))
      (node (ref "U$1") (pin "7") (pinfunction "7_7") (pintype "bidirectional"))
    )
    (net (code "5") (name "/C4") (class "Default")
      (node (ref "1") (pin "MX2") (pinfunction "P1_MX2") (pintype "bidirectional"))
      (node (ref "A") (pin "MX2") (pinfunction "P1_MX2") (pintype "bidirectional"))
      (node (ref "EXCLAMATION") (pin "MX2") (pinfunction "P1_MX2") (pintype "bidirectional"))
      (node (ref "LEFT_GUI") (pin "MX2") (pinfunction "P1_MX2") (pintype "bidirectional"))
      (node (ref "Q") (pin "MX2") (pinfunction "P1_MX2") (pintype "bidirectional"))
      (node (ref "U$1") (pin "6") (pinfunction "6_6") (pintype "bidirectional"))
      (node (ref "Z") (pin "MX2") (pinfunction "P1_MX2") (pintype "bidirectional"))
    )
    (net (code "6") (name "/C5") (class "Default")
      (node (ref "2") (pin "MX2") (pinfunction "P1_MX2") (pintype "bidirectional"))
      (node (ref "AT") (pin "MX2") (pinfunction "P1_MX2") (pintype "bidirectional"))
      (node (ref "LEFT_ALT") (pin "MX2") (pinfunction "P1_MX2") (pintype "bidirectional"))
      (node (ref "S") (pin "MX2") (pinfunction "P1_MX2") (pintype "bidirectional"))
      (node (ref "U$1") (pin "5") (pinfunction "5_5") (pintype "bidirectional"))
      (node (ref "W") (pin "MX2") (pinfunction "P1_MX2") (pintype "bidirectional"))
      (node (ref "X") (pin "MX2") (pinfunction "P1_MX2") (pintype "bidirectional"))
    )
    (net (code "7") (name "/C6") (class "Default")
      (node (ref "3") (pin "MX2") (pinfunction "P1_MX2") (pintype "bidirectional"))
      (node (ref "C") (pin "MX2") (pinfunction "P1_MX2") (pintype "bidirectional"))
      (node (ref "D") (pin "MX2") (pinfunction "P1_MX2") (pintype "bidirectional"))
      (node (ref "E") (pin "MX2") (pinfunction "P1_MX2") (pintype "bidirectional"))
      (node (ref "HASH") (pin "MX2") (pinfunction "P1_MX2") (pintype "bidirectional"))
      (node (ref "LEFT_SPACE") (pin "MX2") (pinfunction "P1_MX2") (pintype "bidirectional"))
      (node (ref "U$1") (pin "4") (pinfunction "4_4") (pintype "bidirectional"))
    )
    (net (code "8") (name "/C7") (class "Default")
      (node (ref "4") (pin "MX2") (pinfunction "P1_MX2") (pintype "bidirectional"))
      (node (ref "DOLLAR") (pin "MX2") (pinfunction "P1_MX2") (pintype "bidirectional"))
      (node (ref "F") (pin "MX2") (pinfunction "P1_MX2") (pintype "bidirectional"))
      (node (ref "R") (pin "MX2") (pinfunction "P1_MX2") (pintype "bidirectional"))
      (node (ref "U$1") (pin "3") (pinfunction "3_3") (pintype "bidirectional"))
      (node (ref "V") (pin "MX2") (pinfunction "P1_MX2") (pintype "bidirectional"))
    )
    (net (code "9") (name "/C8") (class "Default")
      (node (ref "5") (pin "MX2") (pinfunction "P1_MX2") (pintype "bidirectional"))
      (node (ref "B") (pin "MX2") (pinfunction "P1_MX2") (pintype "bidirectional"))
      (node (ref "FN") (pin "MX2") (pinfunction "P1_MX2") (pintype "bidirectional"))
      (node (ref "G") (pin "MX2") (pinfunction "P1_MX2") (pintype "bidirectional"))
      (node (ref "PERCENT") (pin "MX2") (pinfunction "P1_MX2") (pintype "bidirectional"))
      (node (ref "T") (pin "MX2") (pinfunction "P1_MX2") (pintype "bidirectional"))
      (node (ref "U$1") (pin "2") (pinfunction "2_2") (pintype "bidirectional"))
    )
    (net (code "10") (name "/C9") (class "Default")
      (node (ref "6") (pin "MX2") (pinfunction "P1_MX2") (pintype "bidirectional"))
      (node (ref "CARROT") (pin "MX2") (pinfunction "P1_MX2") (pintype "bidirectional"))
      (node (ref "H") (pin "MX2") (pinfunction "P1_MX2") (pintype "bidirectional"))
      (node (ref "J2") (pin "1") (pinfunction "1_1") (pintype "bidirectional"))
      (node (ref "N") (pin "MX2") (pinfunction "P1_MX2") (pintype "bidirectional"))
      (node (ref "RIGHT_SPACE") (pin "MX2") (pinfunction "P1_MX2") (pintype "bidirectional"))
      (node (ref "Y") (pin "MX2") (pinfunction "P1_MX2") (pintype "bidirectional"))
    )
    (net (code "11") (name "/C10") (class "Default")
      (node (ref "7") (pin "MX2") (pinfunction "P1_MX2") (pintype "bidirectional"))
      (node (ref "AMPERSAND") (pin "MX2") (pinfunction "P1_MX2") (pintype "bidirectional"))
      (node (ref "J") (pin "MX2") (pinfunction "P1_MX2") (pintype "bidirectional"))
      (node (ref "J2") (pin "2") (pinfunction "2_2") (pintype "bidirectional"))
      (node (ref "M") (pin "MX2") (pinfunction "P1_MX2") (pintype "bidirectional"))
      (node (ref "U") (pin "MX2") (pinfunction "P1_MX2") (pintype "bidirectional"))
    )
    (net (code "12") (name "/C11") (class "Default")
      (node (ref "8") (pin "MX2") (pinfunction "P1_MX2") (pintype "bidirectional"))
      (node (ref "ASTERICK") (pin "MX2") (pinfunction "P1_MX2") (pintype "bidirectional"))
      (node (ref "COMMA") (pin "MX2") (pinfunction "P1_MX2") (pintype "bidirectional"))
      (node (ref "I") (pin "MX2") (pinfunction "P1_MX2") (pintype "bidirectional"))
      (node (ref "J2") (pin "5") (pinfunction "5_5") (pintype "bidirectional"))
      (node (ref "K") (pin "MX2") (pinfunction "P1_MX2") (pintype "bidirectional"))
      (node (ref "LESS_GREATER") (pin "MX2") (pinfunction "P1_MX2") (pintype "bidirectional"))
    )
    (net (code "13") (name "/C12") (class "Default")
      (node (ref "9") (pin "MX2") (pinfunction "P1_MX2") (pintype "bidirectional"))
      (node (ref "GREATER_LESS") (pin "MX2") (pinfunction "P1_MX2") (pintype "bidirectional"))
      (node (ref "J2") (pin "12") (pinfunction "12_12") (pintype "bidirectional"))
      (node (ref "L") (pin "MX2") (pinfunction "P1_MX2") (pintype "bidirectional"))
      (node (ref "LEFT_PAREN") (pin "MX2") (pinfunction "P1_MX2") (pintype "bidirectional"))
      (node (ref "O") (pin "MX2") (pinfunction "P1_MX2") (pintype "bidirectional"))
      (node (ref "PERIOD") (pin "MX2") (pinfunction "P1_MX2") (pintype "bidirectional"))
    )
    (net (code "14") (name "/C13") (class "Default")
      (node (ref "0") (pin "MX2") (pinfunction "P1_MX2") (pintype "bidirectional"))
      (node (ref "COLON") (pin "MX2") (pinfunction "P1_MX2") (pintype "bidirectional"))
      (node (ref "FORWARD_SLASH") (pin "MX2") (pinfunction "P1_MX2") (pintype "bidirectional"))
      (node (ref "J2") (pin "11") (pinfunction "11_11") (pintype "bidirectional"))
      (node (ref "P") (pin "MX2") (pinfunction "P1_MX2") (pintype "bidirectional"))
      (node (ref "QUESTION_MARK") (pin "MX2") (pinfunction "P1_MX2") (pintype "bidirectional"))
      (node (ref "RIGHT_PAREN") (pin "MX2") (pinfunction "P1_MX2") (pintype "bidirectional"))
    )
    (net (code "15") (name "/C14") (class "Default")
      (node (ref "ARROW_LEFT") (pin "MX2") (pinfunction "P1_MX2") (pintype "bidirectional"))
      (node (ref "J2") (pin "10") (pinfunction "10_10") (pintype "bidirectional"))
      (node (ref "LEFT_BRACKET") (pin "MX2") (pinfunction "P1_MX2") (pintype "bidirectional"))
      (node (ref "MINUS") (pin "MX2") (pinfunction "P1_MX2") (pintype "bidirectional"))
      (node (ref "RIGHT_SHIFT") (pin "MX2") (pinfunction "P1_MX2") (pintype "bidirectional"))
      (node (ref "SINGE_QUOTE") (pin "MX2") (pinfunction "P1_MX2") (pintype "bidirectional"))
      (node (ref "UNDESCORE") (pin "MX2") (pinfunction "P1_MX2") (pintype "bidirectional"))
    )
    (net (code "16") (name "/C15") (class "Default")
      (node (ref "ARROW_DOWN") (pin "MX2") (pinfunction "P1_MX2") (pintype "bidirectional"))
      (node (ref "ARROW_UP") (pin "MX2") (pinfunction "P1_MX2") (pintype "bidirectional"))
      (node (ref "ENTER") (pin "MX2") (pinfunction "P1_MX2") (pintype "bidirectional"))
      (node (ref "EQUALS") (pin "MX2") (pinfunction "P1_MX2") (pintype "bidirectional"))
      (node (ref "J2") (pin "9") (pinfunction "9_9") (pintype "bidirectional"))
      (node (ref "PLUS") (pin "MX2") (pinfunction "P1_MX2") (pintype "bidirectional"))
      (node (ref "RIGHT_BRACKET") (pin "MX2") (pinfunction "P1_MX2") (pintype "bidirectional"))
    )
    (net (code "17") (name "/C16") (class "Default")
      (node (ref "ARROW_RIGHT") (pin "MX2") (pinfunction "P1_MX2") (pintype "bidirectional"))
      (node (ref "BACKSPACE") (pin "MX2") (pinfunction "P1_MX2") (pintype "bidirectional"))
      (node (ref "BACK_SLASH") (pin "MX2") (pinfunction "P1_MX2") (pintype "bidirectional"))
      (node (ref "DELETE") (pin "MX2") (pinfunction "P1_MX2") (pintype "bidirectional"))
      (node (ref "J2") (pin "8") (pinfunction "8_8") (pintype "bidirectional"))
      (node (ref "NUMPAD_0") (pin "MX2") (pinfunction "P1_MX2") (pintype "bidirectional"))
    )
    (net (code "18") (name "/C17") (class "Default")
      (node (ref "HOME") (pin "MX2") (pinfunction "P1_MX2") (pintype "bidirectional"))
      (node (ref "J2") (pin "7") (pinfunction "7_7") (pintype "bidirectional"))
      (node (ref "LEFT_CBRACE") (pin "MX2") (pinfunction "P1_MX2") (pintype "bidirectional"))
      (node (ref "NUMPAD_1") (pin "MX2") (pinfunction "P1_MX2") (pintype "bidirectional"))
      (node (ref "NUMPAD_4") (pin "MX2") (pinfunction "P1_MX2") (pintype "bidirectional"))
      (node (ref "NUMPAD_7") (pin "MX2") (pinfunction "P1_MX2") (pintype "bidirectional"))
      (node (ref "SEMICOLON") (pin "MX2") (pinfunction "P1_MX2") (pintype "bidirectional"))
    )
    (net (code "19") (name "/C18") (class "Default")
      (node (ref "DBL_QUOTE") (pin "MX2") (pinfunction "P1_MX2") (pintype "bidirectional"))
      (node (ref "END") (pin "MX2") (pinfunction "P1_MX2") (pintype "bidirectional"))
      (node (ref "J2") (pin "6") (pinfunction "6_6") (pintype "bidirectional"))
      (node (ref "NUMPAD_2") (pin "MX2") (pinfunction "P1_MX2") (pintype "bidirectional"))
      (node (ref "NUMPAD_5") (pin "MX2") (pinfunction "P1_MX2") (pintype "bidirectional"))
      (node (ref "NUMPAD_8") (pin "MX2") (pinfunction "P1_MX2") (pintype "bidirectional"))
      (node (ref "RIGHT_CBRACE") (pin "MX2") (pinfunction "P1_MX2") (pintype "bidirectional"))
    )
    (net (code "20") (name "/C19") (class "Default")
      (node (ref "J1") (pin "12") (pinfunction "12_12") (pintype "bidirectional"))
      (node (ref "NUMPAD_3") (pin "MX2") (pinfunction "P1_MX2") (pintype "bidirectional"))
      (node (ref "NUMPAD_6") (pin "MX2") (pinfunction "P1_MX2") (pintype "bidirectional"))
      (node (ref "NUMPAD_9") (pin "MX2") (pinfunction "P1_MX2") (pintype "bidirectional"))
      (node (ref "PG_DOWN") (pin "MX2") (pinfunction "P1_MX2") (pintype "bidirectional"))
      (node (ref "PG_UP") (pin "MX2") (pinfunction "P1_MX2") (pintype "bidirectional"))
      (node (ref "PIPE") (pin "MX2") (pinfunction "P1_MX2") (pintype "bidirectional"))
    )
    (net (code "21") (name "/R0") (class "Default")
      (node (ref "D1") (pin "C") (pinfunction "C_C") (pintype "passive"))
      (node (ref "D10") (pin "C") (pinfunction "C_C") (pintype "passive"))
      (node (ref "D11") (pin "C") (pinfunction "C_C") (pintype "passive"))
      (node (ref "D12") (pin "C") (pinfunction "C_C") (pintype "passive"))
      (node (ref "D13") (pin "C") (pinfunction "C_C") (pintype "passive"))
      (node (ref "D14") (pin "C") (pinfunction "C_C") (pintype "passive"))
      (node (ref "D15") (pin "C") (pinfunction "C_C") (pintype "passive"))
      (node (ref "D16") (pin "C") (pinfunction "C_C") (pintype "passive"))
      (node (ref "D17") (pin "C") (pinfunction "C_C") (pintype "passive"))
      (node (ref "D18") (pin "C") (pinfunction "C_C") (pintype "passive"))
      (node (ref "D19") (pin "C") (pinfunction "C_C") (pintype "passive"))
      (node (ref "D2") (pin "C") (pinfunction "C_C") (pintype "passive"))
      (node (ref "D20") (pin "C") (pinfunction "C_C") (pintype "passive"))
      (node (ref "D3") (pin "C") (pinfunction "C_C") (pintype "passive"))
      (node (ref "D4") (pin "C") (pinfunction "C_C") (pintype "passive"))
      (node (ref "D5") (pin "C") (pinfunction "C_C") (pintype "passive"))
      (node (ref "D6") (pin "C") (pinfunction "C_C") (pintype "passive"))
      (node (ref "D7") (pin "C") (pinfunction "C_C") (pintype "passive"))
      (node (ref "D8") (pin "C") (pinfunction "C_C") (pintype "passive"))
      (node (ref "D9") (pin "C") (pinfunction "C_C") (pintype "passive"))
      (node (ref "U$2") (pin "2") (pinfunction "2_2") (pintype "bidirectional"))
    )
    (net (code "22") (name "/R1") (class "Default")
      (node (ref "D21") (pin "C") (pinfunction "C_C") (pintype "passive"))
      (node (ref "D22") (pin "C") (pinfunction "C_C") (pintype "passive"))
      (node (ref "D23") (pin "C") (pinfunction "C_C") (pintype "passive"))
      (node (ref "D24") (pin "C") (pinfunction "C_C") (pintype "passive"))
      (node (ref "D25") (pin "C") (pinfunction "C_C") (pintype "passive"))
      (node (ref "D26") (pin "C") (pinfunction "C_C") (pintype "passive"))
      (node (ref "D27") (pin "C") (pinfunction "C_C") (pintype "passive"))
      (node (ref "D28") (pin "C") (pinfunction "C_C") (pintype "passive"))
      (node (ref "D29") (pin "C") (pinfunction "C_C") (pintype "passive"))
      (node (ref "D30") (pin "C") (pinfunction "C_C") (pintype "passive"))
      (node (ref "D31") (pin "C") (pinfunction "C_C") (pintype "passive"))
      (node (ref "D32") (pin "C") (pinfunction "C_C") (pintype "passive"))
      (node (ref "D33") (pin "C") (pinfunction "C_C") (pintype "passive"))
      (node (ref "D34") (pin "C") (pinfunction "C_C") (pintype "passive"))
      (node (ref "D35") (pin "C") (pinfunction "C_C") (pintype "passive"))
      (node (ref "D36") (pin "C") (pinfunction "C_C") (pintype "passive"))
      (node (ref "D37") (pin "C") (pinfunction "C_C") (pintype "passive"))
      (node (ref "D38") (pin "C") (pinfunction "C_C") (pintype "passive"))
      (node (ref "D39") (pin "C") (pinfunction "C_C") (pintype "passive"))
      (node (ref "D40") (pin "C") (pinfunction "C_C") (pintype "passive"))
      (node (ref "U$2") (pin "3") (pinfunction "3_3") (pintype "bidirectional"))
    )
    (net (code "23") (name "/R2") (class "Default")
      (node (ref "D41") (pin "C") (pinfunction "C_C") (pintype "passive"))
      (node (ref "D42") (pin "C") (pinfunction "C_C") (pintype "passive"))
      (node (ref "D43") (pin "C") (pinfunction "C_C") (pintype "passive"))
      (node (ref "D44") (pin "C") (pinfunction "C_C") (pintype "passive"))
      (node (ref "D45") (pin "C") (pinfunction "C_C") (pintype "passive"))
      (node (ref "D46") (pin "C") (pinfunction "C_C") (pintype "passive"))
      (node (ref "D47") (pin "C") (pinfunction "C_C") (pintype "passive"))
      (node (ref "D48") (pin "C") (pinfunction "C_C") (pintype "passive"))
      (node (ref "D49") (pin "C") (pinfunction "C_C") (pintype "passive"))
      (node (ref "D50") (pin "C") (pinfunction "C_C") (pintype "passive"))
      (node (ref "D51") (pin "C") (pinfunction "C_C") (pintype "passive"))
      (node (ref "D52") (pin "C") (pinfunction "C_C") (pintype "passive"))
      (node (ref "D53") (pin "C") (pinfunction "C_C") (pintype "passive"))
      (node (ref "D54") (pin "C") (pinfunction "C_C") (pintype "passive"))
      (node (ref "D55") (pin "C") (pinfunction "C_C") (pintype "passive"))
      (node (ref "D56") (pin "C") (pinfunction "C_C") (pintype "passive"))
      (node (ref "D57") (pin "C") (pinfunction "C_C") (pintype "passive"))
      (node (ref "D58") (pin "C") (pinfunction "C_C") (pintype "passive"))
      (node (ref "D59") (pin "C") (pinfunction "C_C") (pintype "passive"))
      (node (ref "D60") (pin "C") (pinfunction "C_C") (pintype "passive"))
      (node (ref "U$2") (pin "4") (pinfunction "4_4") (pintype "bidirectional"))
    )
    (net (code "24") (name "/R3") (class "Default")
      (node (ref "D61") (pin "C") (pinfunction "C_C") (pintype "passive"))
      (node (ref "D62") (pin "C") (pinfunction "C_C") (pintype "passive"))
      (node (ref "D63") (pin "C") (pinfunction "C_C") (pintype "passive"))
      (node (ref "D64") (pin "C") (pinfunction "C_C") (pintype "passive"))
      (node (ref "D65") (pin "C") (pinfunction "C_C") (pintype "passive"))
      (node (ref "D66") (pin "C") (pinfunction "C_C") (pintype "passive"))
      (node (ref "D67") (pin "C") (pinfunction "C_C") (pintype "passive"))
      (node (ref "D68") (pin "C") (pinfunction "C_C") (pintype "passive"))
      (node (ref "D69") (pin "C") (pinfunction "C_C") (pintype "passive"))
      (node (ref "D70") (pin "C") (pinfunction "C_C") (pintype "passive"))
      (node (ref "D71") (pin "C") (pinfunction "C_C") (pintype "passive"))
      (node (ref "D72") (pin "C") (pinfunction "C_C") (pintype "passive"))
      (node (ref "D73") (pin "C") (pinfunction "C_C") (pintype "passive"))
      (node (ref "D74") (pin "C") (pinfunction "C_C") (pintype "passive"))
      (node (ref "D75") (pin "C") (pinfunction "C_C") (pintype "passive"))
      (node (ref "D76") (pin "C") (pinfunction "C_C") (pintype "passive"))
      (node (ref "D78") (pin "C") (pinfunction "C_C") (pintype "passive"))
      (node (ref "D79") (pin "C") (pinfunction "C_C") (pintype "passive"))
      (node (ref "D80") (pin "C") (pinfunction "C_C") (pintype "passive"))
      (node (ref "U$2") (pin "5") (pinfunction "5_5") (pintype "bidirectional"))
    )
    (net (code "25") (name "/R4") (class "Default")
      (node (ref "D100") (pin "C") (pinfunction "C_C") (pintype "passive"))
      (node (ref "D81") (pin "C") (pinfunction "C_C") (pintype "passive"))
      (node (ref "D82") (pin "C") (pinfunction "C_C") (pintype "passive"))
      (node (ref "D83") (pin "C") (pinfunction "C_C") (pintype "passive"))
      (node (ref "D84") (pin "C") (pinfunction "C_C") (pintype "passive"))
      (node (ref "D85") (pin "C") (pinfunction "C_C") (pintype "passive"))
      (node (ref "D86") (pin "C") (pinfunction "C_C") (pintype "passive"))
      (node (ref "D87") (pin "C") (pinfunction "C_C") (pintype "passive"))
      (node (ref "D88") (pin "C") (pinfunction "C_C") (pintype "passive"))
      (node (ref "D89") (pin "C") (pinfunction "C_C") (pintype "passive"))
      (node (ref "D90") (pin "C") (pinfunction "C_C") (pintype "passive"))
      (node (ref "D91") (pin "C") (pinfunction "C_C") (pintype "passive"))
      (node (ref "D92") (pin "C") (pinfunction "C_C") (pintype "passive"))
      (node (ref "D93") (pin "C") (pinfunction "C_C") (pintype "passive"))
      (node (ref "D94") (pin "C") (pinfunction "C_C") (pintype "passive"))
      (node (ref "D95") (pin "C") (pinfunction "C_C") (pintype "passive"))
      (node (ref "D96") (pin "C") (pinfunction "C_C") (pintype "passive"))
      (node (ref "D97") (pin "C") (pinfunction "C_C") (pintype "passive"))
      (node (ref "D98") (pin "C") (pinfunction "C_C") (pintype "passive"))
      (node (ref "D99") (pin "C") (pinfunction "C_C") (pintype "passive"))
      (node (ref "U$2") (pin "6") (pinfunction "6_6") (pintype "bidirectional"))
    )
    (net (code "26") (name "/R5") (class "Default")
      (node (ref "D101") (pin "C") (pinfunction "C_C") (pintype "passive"))
      (node (ref "D102") (pin "C") (pinfunction "C_C") (pintype "passive"))
      (node (ref "D103") (pin "C") (pinfunction "C_C") (pintype "passive"))
      (node (ref "D104") (pin "C") (pinfunction "C_C") (pintype "passive"))
      (node (ref "D105") (pin "C") (pinfunction "C_C") (pintype "passive"))
      (node (ref "D106") (pin "C") (pinfunction "C_C") (pintype "passive"))
      (node (ref "D107") (pin "C") (pinfunction "C_C") (pintype "passive"))
      (node (ref "D109") (pin "C") (pinfunction "C_C") (pintype "passive"))
      (node (ref "D110") (pin "C") (pinfunction "C_C") (pintype "passive"))
      (node (ref "D112") (pin "C") (pinfunction "C_C") (pintype "passive"))
      (node (ref "D113") (pin "C") (pinfunction "C_C") (pintype "passive"))
      (node (ref "D114") (pin "C") (pinfunction "C_C") (pintype "passive"))
      (node (ref "D115") (pin "C") (pinfunction "C_C") (pintype "passive"))
      (node (ref "D116") (pin "C") (pinfunction "C_C") (pintype "passive"))
      (node (ref "D117") (pin "C") (pinfunction "C_C") (pintype "passive"))
      (node (ref "D118") (pin "C") (pinfunction "C_C") (pintype "passive"))
      (node (ref "D119") (pin "C") (pinfunction "C_C") (pintype "passive"))
      (node (ref "D120") (pin "C") (pinfunction "C_C") (pintype "passive"))
      (node (ref "U$2") (pin "7") (pinfunction "7_7") (pintype "bidirectional"))
    )
    (net (code "27") (name "Net-(0-P0)") (class "Default")
      (node (ref "0") (pin "MX1") (pinfunction "P0_MX1") (pintype "bidirectional"))
      (node (ref "D34") (pin "A") (pinfunction "A_A") (pintype "passive"))
    )
    (net (code "28") (name "Net-(1-P0)") (class "Default")
      (node (ref "1") (pin "MX1") (pinfunction "P0_MX1") (pintype "bidirectional"))
      (node (ref "D25") (pin "A") (pinfunction "A_A") (pintype "passive"))
    )
    (net (code "29") (name "Net-(2-P0)") (class "Default")
      (node (ref "2") (pin "MX1") (pinfunction "P0_MX1") (pintype "bidirectional"))
      (node (ref "D26") (pin "A") (pinfunction "A_A") (pintype "passive"))
    )
    (net (code "30") (name "Net-(3-P0)") (class "Default")
      (node (ref "3") (pin "MX1") (pinfunction "P0_MX1") (pintype "bidirectional"))
      (node (ref "D27") (pin "A") (pinfunction "A_A") (pintype "passive"))
    )
    (net (code "31") (name "Net-(4-P0)") (class "Default")
      (node (ref "4") (pin "MX1") (pinfunction "P0_MX1") (pintype "bidirectional"))
      (node (ref "D28") (pin "A") (pinfunction "A_A") (pintype "passive"))
    )
    (net (code "32") (name "Net-(5-P0)") (class "Default")
      (node (ref "5") (pin "MX1") (pinfunction "P0_MX1") (pintype "bidirectional"))
      (node (ref "D29") (pin "A") (pinfunction "A_A") (pintype "passive"))
    )
    (net (code "33") (name "Net-(6-P0)") (class "Default")
      (node (ref "6") (pin "MX1") (pinfunction "P0_MX1") (pintype "bidirectional"))
      (node (ref "D30") (pin "A") (pinfunction "A_A") (pintype "passive"))
    )
    (net (code "34") (name "Net-(7-P0)") (class "Default")
      (node (ref "7") (pin "MX1") (pinfunction "P0_MX1") (pintype "bidirectional"))
      (node (ref "D31") (pin "A") (pinfunction "A_A") (pintype "passive"))
    )
    (net (code "35") (name "Net-(8-P0)") (class "Default")
      (node (ref "8") (pin "MX1") (pinfunction "P0_MX1") (pintype "bidirectional"))
      (node (ref "D32") (pin "A") (pinfunction "A_A") (pintype "passive"))
    )
    (net (code "36") (name "Net-(9-P0)") (class "Default")
      (node (ref "9") (pin "MX1") (pinfunction "P0_MX1") (pintype "bidirectional"))
      (node (ref "D33") (pin "A") (pinfunction "A_A") (pintype "passive"))
    )
    (net (code "37") (name "Net-(A-P0)") (class "Default")
      (node (ref "A") (pin "MX1") (pinfunction "P0_MX1") (pintype "bidirectional"))
      (node (ref "D65") (pin "A") (pinfunction "A_A") (pintype "passive"))
    )
    (net (code "38") (name "Net-(AMPERSAND-P0)") (class "Default")
      (node (ref "AMPERSAND") (pin "MX1") (pinfunction "P0_MX1") (pintype "bidirectional"))
      (node (ref "D11") (pin "A") (pinfunction "A_A") (pintype "passive"))
    )
    (net (code "39") (name "Net-(ARROW_DOWN-P0)") (class "Default")
      (node (ref "ARROW_DOWN") (pin "MX1") (pinfunction "P0_MX1") (pintype "bidirectional"))
      (node (ref "D116") (pin "A") (pinfunction "A_A") (pintype "passive"))
    )
    (net (code "40") (name "Net-(ARROW_LEFT-P0)") (class "Default")
      (node (ref "ARROW_LEFT") (pin "MX1") (pinfunction "P0_MX1") (pintype "bidirectional"))
      (node (ref "D115") (pin "A") (pinfunction "A_A") (pintype "passive"))
    )
    (net (code "41") (name "Net-(ARROW_RIGHT-P0)") (class "Default")
      (node (ref "ARROW_RIGHT") (pin "MX1") (pinfunction "P0_MX1") (pintype "bidirectional"))
      (node (ref "D117") (pin "A") (pinfunction "A_A") (pintype "passive"))
    )
    (net (code "42") (name "Net-(ARROW_UP-P0)") (class "Default")
      (node (ref "ARROW_UP") (pin "MX1") (pinfunction "P0_MX1") (pintype "bidirectional"))
      (node (ref "D96") (pin "A") (pinfunction "A_A") (pintype "passive"))
    )
    (net (code "43") (name "Net-(ASTERICK-P0)") (class "Default")
      (node (ref "ASTERICK") (pin "MX1") (pinfunction "P0_MX1") (pintype "bidirectional"))
      (node (ref "D12") (pin "A") (pinfunction "A_A") (pintype "passive"))
    )
    (net (code "44") (name "Net-(AT-P0)") (class "Default")
      (node (ref "AT") (pin "MX1") (pinfunction "P0_MX1") (pintype "bidirectional"))
      (node (ref "D6") (pin "A") (pinfunction "A_A") (pintype "passive"))
    )
    (net (code "45") (name "Net-(B-P0)") (class "Default")
      (node (ref "B") (pin "MX1") (pinfunction "P0_MX1") (pintype "bidirectional"))
      (node (ref "D89") (pin "A") (pinfunction "A_A") (pintype "passive"))
    )
    (net (code "46") (name "Net-(BACKSPACE-P0)") (class "Default")
      (node (ref "BACKSPACE") (pin "MX1") (pinfunction "P0_MX1") (pintype "bidirectional"))
      (node (ref "D37") (pin "A") (pinfunction "A_A") (pintype "passive"))
    )
    (net (code "47") (name "Net-(BACK_SLASH-P0)") (class "Default")
      (node (ref "BACK_SLASH") (pin "MX1") (pinfunction "P0_MX1") (pintype "bidirectional"))
      (node (ref "D57") (pin "A") (pinfunction "A_A") (pintype "passive"))
    )
    (net (code "48") (name "Net-(C-P0)") (class "Default")
      (node (ref "C") (pin "MX1") (pinfunction "P0_MX1") (pintype "bidirectional"))
      (node (ref "D87") (pin "A") (pinfunction "A_A") (pintype "passive"))
    )
    (net (code "49") (name "Net-(CAPS_LOCK-P0)") (class "Default")
      (node (ref "CAPS_LOCK") (pin "MX1") (pinfunction "P0_MX1") (pintype "bidirectional"))
      (node (ref "D64") (pin "A") (pinfunction "A_A") (pintype "passive"))
    )
    (net (code "50") (name "Net-(CARROT-P0)") (class "Default")
      (node (ref "CARROT") (pin "MX1") (pinfunction "P0_MX1") (pintype "bidirectional"))
      (node (ref "D10") (pin "A") (pinfunction "A_A") (pintype "passive"))
    )
    (net (code "51") (name "Net-(COLON-P0)") (class "Default")
      (node (ref "COLON") (pin "MX1") (pinfunction "P0_MX1") (pintype "bidirectional"))
      (node (ref "D74") (pin "A") (pinfunction "A_A") (pintype "passive"))
    )
    (net (code "52") (name "Net-(COMMA-P0)") (class "Default")
      (node (ref "COMMA") (pin "MX1") (pinfunction "P0_MX1") (pintype "bidirectional"))
      (node (ref "D112") (pin "A") (pinfunction "A_A") (pintype "passive"))
    )
    (net (code "53") (name "Net-(COPY-P0)") (class "Default")
      (node (ref "COPY") (pin "MX1") (pinfunction "P0_MX1") (pintype "bidirectional"))
      (node (ref "D102") (pin "A") (pinfunction "A_A") (pintype "passive"))
    )
    (net (code "54") (name "Net-(CUT-P0)") (class "Default")
      (node (ref "CUT") (pin "MX1") (pinfunction "P0_MX1") (pintype "bidirectional"))
      (node (ref "D101") (pin "A") (pinfunction "A_A") (pintype "passive"))
    )
    (net (code "55") (name "Net-(D-P0)") (class "Default")
      (node (ref "D") (pin "MX1") (pinfunction "P0_MX1") (pintype "bidirectional"))
      (node (ref "D67") (pin "A") (pinfunction "A_A") (pintype "passive"))
    )
    (net (code "56") (name "Net-(DBL_QUOTE-P0)") (class "Default")
      (node (ref "D59") (pin "A") (pinfunction "A_A") (pintype "passive"))
      (node (ref "DBL_QUOTE") (pin "MX1") (pinfunction "P0_MX1") (pintype "bidirectional"))
    )
    (net (code "57") (name "Net-(DELETE-P0)") (class "Default")
      (node (ref "D17") (pin "A") (pinfunction "A_A") (pintype "passive"))
      (node (ref "DELETE") (pin "MX1") (pinfunction "P0_MX1") (pintype "bidirectional"))
    )
    (net (code "58") (name "Net-(DOLLAR-P0)") (class "Default")
      (node (ref "D8") (pin "A") (pinfunction "A_A") (pintype "passive"))
      (node (ref "DOLLAR") (pin "MX1") (pinfunction "P0_MX1") (pintype "bidirectional"))
    )
    (net (code "59") (name "Net-(E-P0)") (class "Default")
      (node (ref "D47") (pin "A") (pinfunction "A_A") (pintype "passive"))
      (node (ref "E") (pin "MX1") (pinfunction "P0_MX1") (pintype "bidirectional"))
    )
    (net (code "60") (name "Net-(END-P0)") (class "Default")
      (node (ref "D39") (pin "A") (pinfunction "A_A") (pintype "passive"))
      (node (ref "END") (pin "MX1") (pinfunction "P0_MX1") (pintype "bidirectional"))
    )
    (net (code "61") (name "Net-(ENTER-P0)") (class "Default")
      (node (ref "D76") (pin "A") (pinfunction "A_A") (pintype "passive"))
      (node (ref "ENTER") (pin "MX1") (pinfunction "P0_MX1") (pintype "bidirectional"))
    )
    (net (code "62") (name "Net-(EQUALS-P0)") (class "Default")
      (node (ref "D36") (pin "A") (pinfunction "A_A") (pintype "passive"))
      (node (ref "EQUALS") (pin "MX1") (pinfunction "P0_MX1") (pintype "bidirectional"))
    )
    (net (code "63") (name "Net-(ESCAPE-P0)") (class "Default")
      (node (ref "D24") (pin "A") (pinfunction "A_A") (pintype "passive"))
      (node (ref "ESCAPE") (pin "MX1") (pinfunction "P0_MX1") (pintype "bidirectional"))
    )
    (net (code "64") (name "Net-(EXCLAMATION-P0)") (class "Default")
      (node (ref "D5") (pin "A") (pinfunction "A_A") (pintype "passive"))
      (node (ref "EXCLAMATION") (pin "MX1") (pinfunction "P0_MX1") (pintype "bidirectional"))
    )
    (net (code "65") (name "Net-(F-P0)") (class "Default")
      (node (ref "D68") (pin "A") (pinfunction "A_A") (pintype "passive"))
      (node (ref "F") (pin "MX1") (pinfunction "P0_MX1") (pintype "bidirectional"))
    )
    (net (code "66") (name "Net-(F1-P0)") (class "Default")
      (node (ref "D61") (pin "A") (pinfunction "A_A") (pintype "passive"))
      (node (ref "F1") (pin "MX1") (pinfunction "P0_MX1") (pintype "bidirectional"))
    )
    (net (code "67") (name "Net-(F2-P0)") (class "Default")
      (node (ref "D41") (pin "A") (pinfunction "A_A") (pintype "passive"))
      (node (ref "F2") (pin "MX1") (pinfunction "P0_MX1") (pintype "bidirectional"))
    )
    (net (code "68") (name "Net-(F3-P0)") (class "Default")
      (node (ref "D21") (pin "A") (pinfunction "A_A") (pintype "passive"))
      (node (ref "F3") (pin "MX1") (pinfunction "P0_MX1") (pintype "bidirectional"))
    )
    (net (code "69") (name "Net-(F4-P0)") (class "Default")
      (node (ref "D1") (pin "A") (pinfunction "A_A") (pintype "passive"))
      (node (ref "F4") (pin "MX1") (pinfunction "P0_MX1") (pintype "bidirectional"))
    )
    (net (code "70") (name "Net-(F5-P0)") (class "Default")
      (node (ref "D62") (pin "A") (pinfunction "A_A") (pintype "passive"))
      (node (ref "F5") (pin "MX1") (pinfunction "P0_MX1") (pintype "bidirectional"))
    )
    (net (code "71") (name "Net-(F6-P0)") (class "Default")
      (node (ref "D42") (pin "A") (pinfunction "A_A") (pintype "passive"))
      (node (ref "F6") (pin "MX1") (pinfunction "P0_MX1") (pintype "bidirectional"))
    )
    (net (code "72") (name "Net-(F7-P0)") (class "Default")
      (node (ref "D22") (pin "A") (pinfunction "A_A") (pintype "passive"))
      (node (ref "F7") (pin "MX1") (pinfunction "P0_MX1") (pintype "bidirectional"))
    )
    (net (code "73") (name "Net-(F8-P0)") (class "Default")
      (node (ref "D2") (pin "A") (pinfunction "A_A") (pintype "passive"))
      (node (ref "F8") (pin "MX1") (pinfunction "P0_MX1") (pintype "bidirectional"))
    )
    (net (code "74") (name "Net-(F9-P0)") (class "Default")
      (node (ref "D63") (pin "A") (pinfunction "A_A") (pintype "passive"))
      (node (ref "F9") (pin "MX1") (pinfunction "P0_MX1") (pintype "bidirectional"))
    )
    (net (code "75") (name "Net-(F10-P0)") (class "Default")
      (node (ref "D43") (pin "A") (pinfunction "A_A") (pintype "passive"))
      (node (ref "F10") (pin "MX1") (pinfunction "P0_MX1") (pintype "bidirectional"))
    )
    (net (code "76") (name "Net-(F11-P0)") (class "Default")
      (node (ref "D23") (pin "A") (pinfunction "A_A") (pintype "passive"))
      (node (ref "F11") (pin "MX1") (pinfunction "P0_MX1") (pintype "bidirectional"))
    )
    (net (code "77") (name "Net-(F12-P0)") (class "Default")
      (node (ref "D3") (pin "A") (pinfunction "A_A") (pintype "passive"))
      (node (ref "F12") (pin "MX1") (pinfunction "P0_MX1") (pintype "bidirectional"))
    )
    (net (code "78") (name "Net-(FN-P0)") (class "Default")
      (node (ref "D109") (pin "A") (pinfunction "A_A") (pintype "passive"))
      (node (ref "FN") (pin "MX1") (pinfunction "P0_MX1") (pintype "bidirectional"))
    )
    (net (code "79") (name "Net-(FORWARD_SLASH-P0)") (class "Default")
      (node (ref "D114") (pin "A") (pinfunction "A_A") (pintype "passive"))
      (node (ref "FORWARD_SLASH") (pin "MX1") (pinfunction "P0_MX1") (pintype "bidirectional"))
    )
    (net (code "80") (name "Net-(G-P0)") (class "Default")
      (node (ref "D69") (pin "A") (pinfunction "A_A") (pintype "passive"))
      (node (ref "G") (pin "MX1") (pinfunction "P0_MX1") (pintype "bidirectional"))
    )
    (net (code "81") (name "Net-(GREATER_LESS-P0)") (class "Default")
      (node (ref "D93") (pin "A") (pinfunction "A_A") (pintype "passive"))
      (node (ref "GREATER_LESS") (pin "MX1") (pinfunction "P0_MX1") (pintype "bidirectional"))
    )
    (net (code "82") (name "Net-(H-P0)") (class "Default")
      (node (ref "D70") (pin "A") (pinfunction "A_A") (pintype "passive"))
      (node (ref "H") (pin "MX1") (pinfunction "P0_MX1") (pintype "bidirectional"))
    )
    (net (code "83") (name "Net-(HASH-P0)") (class "Default")
      (node (ref "D7") (pin "A") (pinfunction "A_A") (pintype "passive"))
      (node (ref "HASH") (pin "MX1") (pinfunction "P0_MX1") (pintype "bidirectional"))
    )
    (net (code "84") (name "Net-(HOME-P0)") (class "Default")
      (node (ref "D38") (pin "A") (pinfunction "A_A") (pintype "passive"))
      (node (ref "HOME") (pin "MX1") (pinfunction "P0_MX1") (pintype "bidirectional"))
    )
    (net (code "85") (name "Net-(I-P0)") (class "Default")
      (node (ref "D52") (pin "A") (pinfunction "A_A") (pintype "passive"))
      (node (ref "I") (pin "MX1") (pinfunction "P0_MX1") (pintype "bidirectional"))
    )
    (net (code "86") (name "Net-(J-P0)") (class "Default")
      (node (ref "D71") (pin "A") (pinfunction "A_A") (pintype "passive"))
      (node (ref "J") (pin "MX1") (pinfunction "P0_MX1") (pintype "bidirectional"))
    )
    (net (code "87") (name "Net-(K-P0)") (class "Default")
      (node (ref "D72") (pin "A") (pinfunction "A_A") (pintype "passive"))
      (node (ref "K") (pin "MX1") (pinfunction "P0_MX1") (pintype "bidirectional"))
    )
    (net (code "88") (name "Net-(L-P0)") (class "Default")
      (node (ref "D73") (pin "A") (pinfunction "A_A") (pintype "passive"))
      (node (ref "L") (pin "MX1") (pinfunction "P0_MX1") (pintype "bidirectional"))
    )
    (net (code "89") (name "Net-(LEFT_ALT-P0)") (class "Default")
      (node (ref "D106") (pin "A") (pinfunction "A_A") (pintype "passive"))
      (node (ref "LEFT_ALT") (pin "MX1") (pinfunction "P0_MX1") (pintype "bidirectional"))
    )
    (net (code "90") (name "Net-(LEFT_BRACKET-P0)") (class "Default")
      (node (ref "D55") (pin "A") (pinfunction "A_A") (pintype "passive"))
      (node (ref "LEFT_BRACKET") (pin "MX1") (pinfunction "P0_MX1") (pintype "bidirectional"))
    )
    (net (code "91") (name "Net-(LEFT_CBRACE-P0)") (class "Default")
      (node (ref "D18") (pin "A") (pinfunction "A_A") (pintype "passive"))
      (node (ref "LEFT_CBRACE") (pin "MX1") (pinfunction "P0_MX1") (pintype "bidirectional"))
    )
    (net (code "92") (name "Net-(LEFT_CTRL-P0)") (class "Default")
      (node (ref "D104") (pin "A") (pinfunction "A_A") (pintype "passive"))
      (node (ref "LEFT_CTRL") (pin "MX1") (pinfunction "P0_MX1") (pintype "bidirectional"))
    )
    (net (code "93") (name "Net-(LEFT_GUI-P0)") (class "Default")
      (node (ref "D105") (pin "A") (pinfunction "A_A") (pintype "passive"))
      (node (ref "LEFT_GUI") (pin "MX1") (pinfunction "P0_MX1") (pintype "bidirectional"))
    )
    (net (code "94") (name "Net-(LEFT_PAREN-P0)") (class "Default")
      (node (ref "D13") (pin "A") (pinfunction "A_A") (pintype "passive"))
      (node (ref "LEFT_PAREN") (pin "MX1") (pinfunction "P0_MX1") (pintype "bidirectional"))
    )
    (net (code "95") (name "Net-(LEFT_SHIFT-P0)") (class "Default")
      (node (ref "D84") (pin "A") (pinfunction "A_A") (pintype "passive"))
      (node (ref "LEFT_SHIFT") (pin "MX1") (pinfunction "P0_MX1") (pintype "bidirectional"))
    )
    (net (code "96") (name "Net-(LEFT_SPACE-P0)") (class "Default")
      (node (ref "D107") (pin "A") (pinfunction "A_A") (pintype "passive"))
      (node (ref "LEFT_SPACE") (pin "MX1") (pinfunction "P0_MX1") (pintype "bidirectional"))
    )
    (net (code "97") (name "Net-(LESS_GREATER-P0)") (class "Default")
      (node (ref "D92") (pin "A") (pinfunction "A_A") (pintype "passive"))
      (node (ref "LESS_GREATER") (pin "MX1") (pinfunction "P0_MX1") (pintype "bidirectional"))
    )
    (net (code "98") (name "Net-(M-P0)") (class "Default")
      (node (ref "D91") (pin "A") (pinfunction "A_A") (pintype "passive"))
      (node (ref "M") (pin "MX1") (pinfunction "P0_MX1") (pintype "bidirectional"))
    )
    (net (code "99") (name "Net-(MINUS-P0)") (class "Default")
      (node (ref "D35") (pin "A") (pinfunction "A_A") (pintype "passive"))
      (node (ref "MINUS") (pin "MX1") (pinfunction "P0_MX1") (pintype "bidirectional"))
    )
    (net (code "100") (name "Net-(N-P0)") (class "Default")
      (node (ref "D90") (pin "A") (pinfunction "A_A") (pintype "passive"))
      (node (ref "N") (pin "MX1") (pinfunction "P0_MX1") (pintype "bidirectional"))
    )
    (net (code "101") (name "Net-(NUMPAD_0-P0)") (class "Default")
      (node (ref "D97") (pin "A") (pinfunction "A_A") (pintype "passive"))
      (node (ref "NUMPAD_0") (pin "MX1") (pinfunction "P0_MX1") (pintype "bidirectional"))
    )
    (net (code "102") (name "Net-(NUMPAD_1-P0)") (class "Default")
      (node (ref "D118") (pin "A") (pinfunction "A_A") (pintype "passive"))
      (node (ref "NUMPAD_1") (pin "MX1") (pinfunction "P0_MX1") (pintype "bidirectional"))
    )
    (net (code "103") (name "Net-(NUMPAD_2-P0)") (class "Default")
      (node (ref "D119") (pin "A") (pinfunction "A_A") (pintype "passive"))
      (node (ref "NUMPAD_2") (pin "MX1") (pinfunction "P0_MX1") (pintype "bidirectional"))
    )
    (net (code "104") (name "Net-(NUMPAD_3-P0)") (class "Default")
      (node (ref "D120") (pin "A") (pinfunction "A_A") (pintype "passive"))
      (node (ref "NUMPAD_3") (pin "MX1") (pinfunction "P0_MX1") (pintype "bidirectional"))
    )
    (net (code "105") (name "Net-(NUMPAD_4-P0)") (class "Default")
      (node (ref "D98") (pin "A") (pinfunction "A_A") (pintype "passive"))
      (node (ref "NUMPAD_4") (pin "MX1") (pinfunction "P0_MX1") (pintype "bidirectional"))
    )
    (net (code "106") (name "Net-(NUMPAD_5-P0)") (class "Default")
      (node (ref "D99") (pin "A") (pinfunction "A_A") (pintype "passive"))
      (node (ref "NUMPAD_5") (pin "MX1") (pinfunction "P0_MX1") (pintype "bidirectional"))
    )
    (net (code "107") (name "Net-(NUMPAD_6-P0)") (class "Default")
      (node (ref "D100") (pin "A") (pinfunction "A_A") (pintype "passive"))
      (node (ref "NUMPAD_6") (pin "MX1") (pinfunction "P0_MX1") (pintype "bidirectional"))
    )
    (net (code "108") (name "Net-(NUMPAD_7-P0)") (class "Default")
      (node (ref "D78") (pin "A") (pinfunction "A_A") (pintype "passive"))
      (node (ref "NUMPAD_7") (pin "MX1") (pinfunction "P0_MX1") (pintype "bidirectional"))
    )
    (net (code "109") (name "Net-(NUMPAD_8-P0)") (class "Default")
      (node (ref "D79") (pin "A") (pinfunction "A_A") (pintype "passive"))
      (node (ref "NUMPAD_8") (pin "MX1") (pinfunction "P0_MX1") (pintype "bidirectional"))
    )
    (net (code "110") (name "Net-(NUMPAD_9-P0)") (class "Default")
      (node (ref "D80") (pin "A") (pinfunction "A_A") (pintype "passive"))
      (node (ref "NUMPAD_9") (pin "MX1") (pinfunction "P0_MX1") (pintype "bidirectional"))
    )
    (net (code "111") (name "Net-(O-P0)") (class "Default")
      (node (ref "D53") (pin "A") (pinfunction "A_A") (pintype "passive"))
      (node (ref "O") (pin "MX1") (pinfunction "P0_MX1") (pintype "bidirectional"))
    )
    (net (code "112") (name "Net-(P-P0)") (class "Default")
      (node (ref "D54") (pin "A") (pinfunction "A_A") (pintype "passive"))
      (node (ref "P") (pin "MX1") (pinfunction "P0_MX1") (pintype "bidirectional"))
    )
    (net (code "113") (name "Net-(PASTE-P0)") (class "Default")
      (node (ref "D103") (pin "A") (pinfunction "A_A") (pintype "passive"))
      (node (ref "PASTE") (pin "MX1") (pinfunction "P0_MX1") (pintype "bidirectional"))
    )
    (net (code "114") (name "Net-(PAUSE_BREAK-P0)") (class "Default")
      (node (ref "D83") (pin "A") (pinfunction "A_A") (pintype "passive"))
      (node (ref "PAUSE_BREAK") (pin "MX1") (pinfunction "P0_MX1") (pintype "bidirectional"))
    )
    (net (code "115") (name "Net-(PERCENT-P0)") (class "Default")
      (node (ref "D9") (pin "A") (pinfunction "A_A") (pintype "passive"))
      (node (ref "PERCENT") (pin "MX1") (pinfunction "P0_MX1") (pintype "bidirectional"))
    )
    (net (code "116") (name "Net-(PERIOD-P0)") (class "Default")
      (node (ref "D113") (pin "A") (pinfunction "A_A") (pintype "passive"))
      (node (ref "PERIOD") (pin "MX1") (pinfunction "P0_MX1") (pintype "bidirectional"))
    )
    (net (code "117") (name "Net-(PG_DOWN-P0)") (class "Default")
      (node (ref "D60") (pin "A") (pinfunction "A_A") (pintype "passive"))
      (node (ref "PG_DOWN") (pin "MX1") (pinfunction "P0_MX1") (pintype "bidirectional"))
    )
    (net (code "118") (name "Net-(PG_UP-P0)") (class "Default")
      (node (ref "D40") (pin "A") (pinfunction "A_A") (pintype "passive"))
      (node (ref "PG_UP") (pin "MX1") (pinfunction "P0_MX1") (pintype "bidirectional"))
    )
    (net (code "119") (name "Net-(PIPE-P0)") (class "Default")
      (node (ref "D20") (pin "A") (pinfunction "A_A") (pintype "passive"))
      (node (ref "PIPE") (pin "MX1") (pinfunction "P0_MX1") (pintype "bidirectional"))
    )
    (net (code "120") (name "Net-(PLUS-P0)") (class "Default")
      (node (ref "D16") (pin "A") (pinfunction "A_A") (pintype "passive"))
      (node (ref "PLUS") (pin "MX1") (pinfunction "P0_MX1") (pintype "bidirectional"))
    )
    (net (code "121") (name "Net-(PRINT_SCREEN-P0)") (class "Default")
      (node (ref "D81") (pin "A") (pinfunction "A_A") (pintype "passive"))
      (node (ref "PRINT_SCREEN") (pin "MX1") (pinfunction "P0_MX1") (pintype "bidirectional"))
    )
    (net (code "122") (name "Net-(Q-P0)") (class "Default")
      (node (ref "D45") (pin "A") (pinfunction "A_A") (pintype "passive"))
      (node (ref "Q") (pin "MX1") (pinfunction "P0_MX1") (pintype "bidirectional"))
    )
    (net (code "123") (name "Net-(QUESTION_MARK-P0)") (class "Default")
      (node (ref "D94") (pin "A") (pinfunction "A_A") (pintype "passive"))
      (node (ref "QUESTION_MARK") (pin "MX1") (pinfunction "P0_MX1") (pintype "bidirectional"))
    )
    (net (code "124") (name "Net-(R-P0)") (class "Default")
      (node (ref "D48") (pin "A") (pinfunction "A_A") (pintype "passive"))
      (node (ref "R") (pin "MX1") (pinfunction "P0_MX1") (pintype "bidirectional"))
    )
    (net (code "125") (name "Net-(RIGHT_BRACKET-P0)") (class "Default")
      (node (ref "D56") (pin "A") (pinfunction "A_A") (pintype "passive"))
      (node (ref "RIGHT_BRACKET") (pin "MX1") (pinfunction "P0_MX1") (pintype "bidirectional"))
    )
    (net (code "126") (name "Net-(RIGHT_CBRACE-P0)") (class "Default")
      (node (ref "D19") (pin "A") (pinfunction "A_A") (pintype "passive"))
      (node (ref "RIGHT_CBRACE") (pin "MX1") (pinfunction "P0_MX1") (pintype "bidirectional"))
    )
    (net (code "127") (name "Net-(RIGHT_PAREN-P0)") (class "Default")
      (node (ref "D14") (pin "A") (pinfunction "A_A") (pintype "passive"))
      (node (ref "RIGHT_PAREN") (pin "MX1") (pinfunction "P0_MX1") (pintype "bidirectional"))
    )
    (net (code "128") (name "Net-(RIGHT_SHIFT-P0)") (class "Default")
      (node (ref "D95") (pin "A") (pinfunction "A_A") (pintype "passive"))
      (node (ref "RIGHT_SHIFT") (pin "MX1") (pinfunction "P0_MX1") (pintype "bidirectional"))
    )
    (net (code "129") (name "Net-(RIGHT_SPACE-P0)") (class "Default")
      (node (ref "D110") (pin "A") (pinfunction "A_A") (pintype "passive"))
      (node (ref "RIGHT_SPACE") (pin "MX1") (pinfunction "P0_MX1") (pintype "bidirectional"))
    )
    (net (code "130") (name "Net-(S-P0)") (class "Default")
      (node (ref "D66") (pin "A") (pinfunction "A_A") (pintype "passive"))
      (node (ref "S") (pin "MX1") (pinfunction "P0_MX1") (pintype "bidirectional"))
    )
    (net (code "131") (name "Net-(SCROLL_LOCK-P0)") (class "Default")
      (node (ref "D82") (pin "A") (pinfunction "A_A") (pintype "passive"))
      (node (ref "SCROLL_LOCK") (pin "MX1") (pinfunction "P0_MX1") (pintype "bidirectional"))
    )
    (net (code "132") (name "Net-(SEMICOLON-P0)") (class "Default")
      (node (ref "D58") (pin "A") (pinfunction "A_A") (pintype "passive"))
      (node (ref "SEMICOLON") (pin "MX1") (pinfunction "P0_MX1") (pintype "bidirectional"))
    )
    (net (code "133") (name "Net-(SINGE_QUOTE-P0)") (class "Default")
      (node (ref "D75") (pin "A") (pinfunction "A_A") (pintype "passive"))
      (node (ref "SINGE_QUOTE") (pin "MX1") (pinfunction "P0_MX1") (pintype "bidirectional"))
    )
    (net (code "134") (name "Net-(T-P0)") (class "Default")
      (node (ref "D49") (pin "A") (pinfunction "A_A") (pintype "passive"))
      (node (ref "T") (pin "MX1") (pinfunction "P0_MX1") (pintype "bidirectional"))
    )
    (net (code "135") (name "Net-(TAB-P0)") (class "Default")
      (node (ref "D44") (pin "A") (pinfunction "A_A") (pintype "passive"))
      (node (ref "TAB") (pin "MX1") (pinfunction "P0_MX1") (pintype "bidirectional"))
    )
    (net (code "136") (name "Net-(TILDE-P0)") (class "Default")
      (node (ref "D4") (pin "A") (pinfunction "A_A") (pintype "passive"))
      (node (ref "TILDE") (pin "MX1") (pinfunction "P0_MX1") (pintype "bidirectional"))
    )
    (net (code "137") (name "Net-(U-P0)") (class "Default")
      (node (ref "D51") (pin "A") (pinfunction "A_A") (pintype "passive"))
      (node (ref "U") (pin "MX1") (pinfunction "P0_MX1") (pintype "bidirectional"))
    )
    (net (code "138") (name "Net-(UNDESCORE-P0)") (class "Default")
      (node (ref "D15") (pin "A") (pinfunction "A_A") (pintype "passive"))
      (node (ref "UNDESCORE") (pin "MX1") (pinfunction "P0_MX1") (pintype "bidirectional"))
    )
    (net (code "139") (name "Net-(V-P0)") (class "Default")
      (node (ref "D88") (pin "A") (pinfunction "A_A") (pintype "passive"))
      (node (ref "V") (pin "MX1") (pinfunction "P0_MX1") (pintype "bidirectional"))
    )
    (net (code "140") (name "Net-(W-P0)") (class "Default")
      (node (ref "D46") (pin "A") (pinfunction "A_A") (pintype "passive"))
      (node (ref "W") (pin "MX1") (pinfunction "P0_MX1") (pintype "bidirectional"))
    )
    (net (code "141") (name "Net-(X-P0)") (class "Default")
      (node (ref "D86") (pin "A") (pinfunction "A_A") (pintype "passive"))
      (node (ref "X") (pin "MX1") (pinfunction "P0_MX1") (pintype "bidirectional"))
    )
    (net (code "142") (name "Net-(Y-P0)") (class "Default")
      (node (ref "D50") (pin "A") (pinfunction "A_A") (pintype "passive"))
      (node (ref "Y") (pin "MX1") (pinfunction "P0_MX1") (pintype "bidirectional"))
    )
    (net (code "143") (name "Net-(Z-P0)") (class "Default")
      (node (ref "D85") (pin "A") (pinfunction "A_A") (pintype "passive"))
      (node (ref "Z") (pin "MX1") (pinfunction "P0_MX1") (pintype "bidirectional"))
    )
    (net (code "144") (name "unconnected-(J1-Pad2)") (class "Default")
      (node (ref "J1") (pin "2") (pinfunction "2_2") (pintype "bidirectional"))
    )
    (net (code "145") (name "unconnected-(J1-Pad3)") (class "Default")
      (node (ref "J1") (pin "3") (pinfunction "3_3") (pintype "bidirectional"))
    )
    (net (code "146") (name "unconnected-(J1-Pad4)") (class "Default")
      (node (ref "J1") (pin "4") (pinfunction "4_4") (pintype "bidirectional"))
    )
    (net (code "147") (name "unconnected-(J1-Pad5)") (class "Default")
      (node (ref "J1") (pin "5") (pinfunction "5_5") (pintype "bidirectional"))
    )
    (net (code "148") (name "unconnected-(J1-Pad6)") (class "Default")
      (node (ref "J1") (pin "6") (pinfunction "6_6") (pintype "bidirectional"))
    )
    (net (code "149") (name "unconnected-(J1-Pad7)") (class "Default")
      (node (ref "J1") (pin "7") (pinfunction "7_7") (pintype "bidirectional"))
    )
    (net (code "150") (name "unconnected-(J1-Pad8)") (class "Default")
      (node (ref "J1") (pin "8") (pinfunction "8_8") (pintype "bidirectional"))
    )
    (net (code "151") (name "unconnected-(J1-Pad9)") (class "Default")
      (node (ref "J1") (pin "9") (pinfunction "9_9") (pintype "bidirectional"))
    )
    (net (code "152") (name "unconnected-(J1-Pad10)") (class "Default")
      (node (ref "J1") (pin "10") (pinfunction "10_10") (pintype "bidirectional"))
    )
    (net (code "153") (name "unconnected-(J1-Pad11)") (class "Default")
      (node (ref "J1") (pin "11") (pinfunction "11_11") (pintype "bidirectional"))
    )
    (net (code "154") (name "unconnected-(J2-Pad3)") (class "Default")
      (node (ref "J2") (pin "3") (pinfunction "3_3") (pintype "bidirectional"))
    )
    (net (code "155") (name "unconnected-(J2-Pad4)") (class "Default")
      (node (ref "J2") (pin "4") (pinfunction "4_4") (pintype "bidirectional"))
    )
    (net (code "156") (name "unconnected-(U$1-Pad1)") (class "Default")
      (node (ref "U$1") (pin "1") (pinfunction "1_1") (pintype "bidirectional"))
    )
    (net (code "157") (name "unconnected-(U$2-Pad1)") (class "Default")
      (node (ref "U$2") (pin "1") (pinfunction "1_1") (pintype "bidirectional"))
    )
  )
)
